# Sheet1.net
KiCad netlist of a schematic drawn in Altium Designer
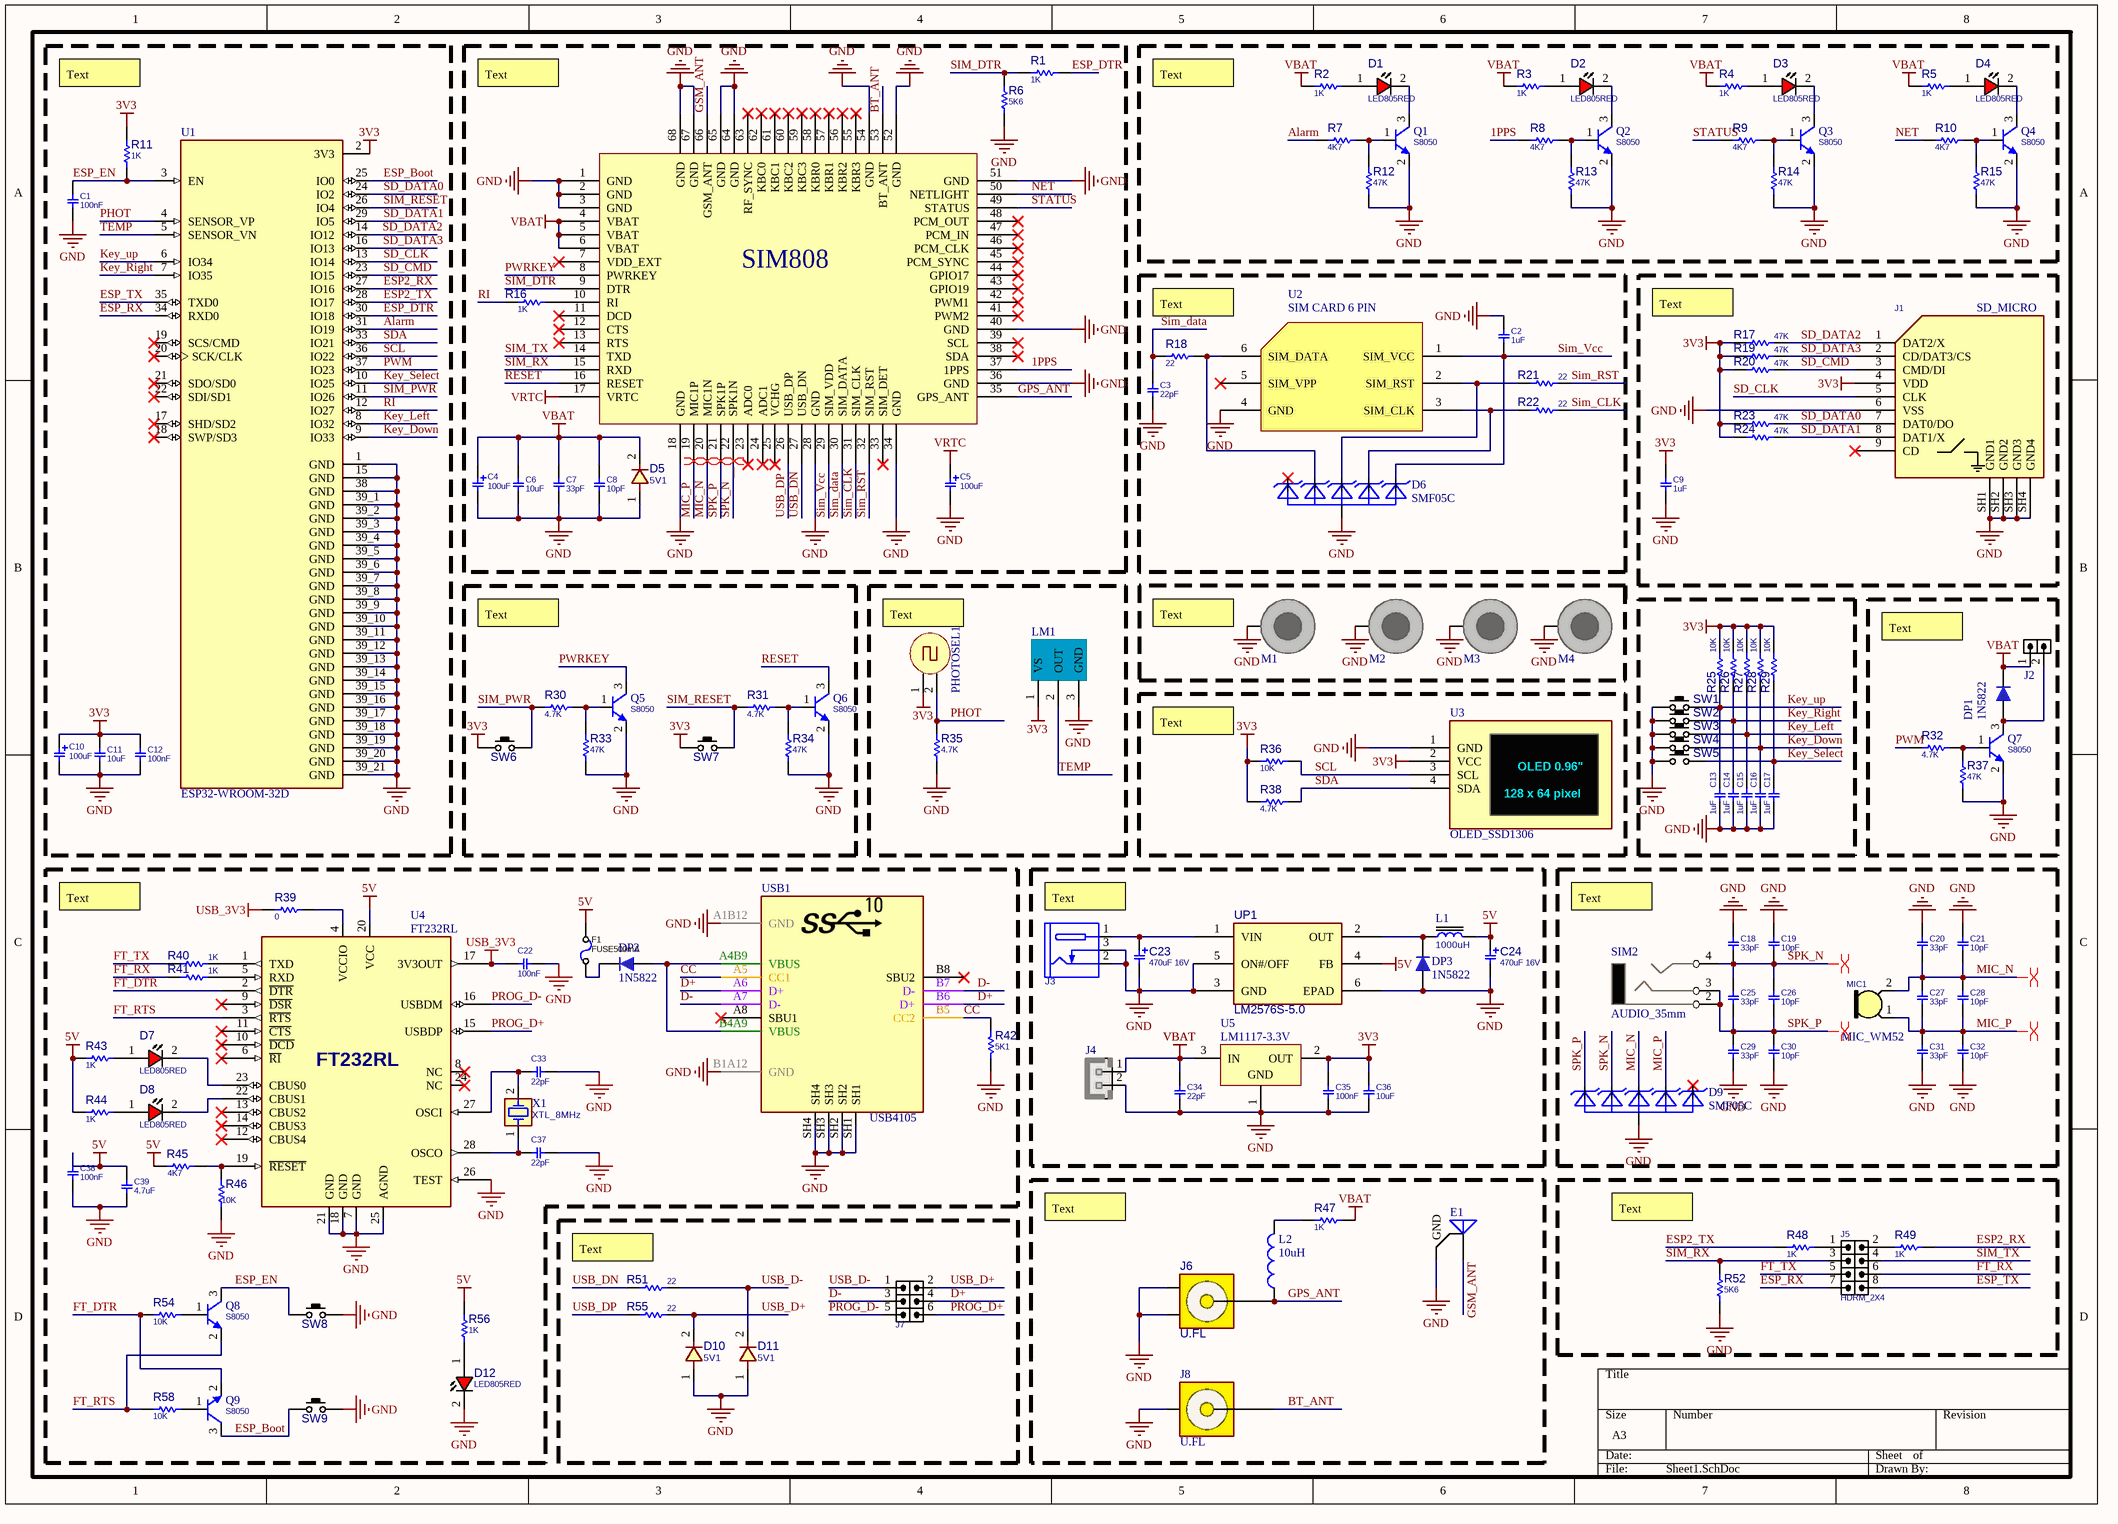
[diagram p0: Sheet1.SchDoc]

(export (version "E")
  (design (tool "Eeschema 10.0.6"))
  (components
    (comp (ref "C1")
      (value "100nF")
      (footprint "C0805")
      (description "CAP, MLCC, -F, -V, MATERIAL, -%, 0201")
      (fields (field (name "MANF_P#") "MANF_PART#"))
      (libsource (lib "Roller shutter") (part "CAP_SMD_MLCC_0805"))
    )
    (comp (ref "C2")
      (value "1uF")
      (footprint "C0805")
      (description "CAP, MLCC, -F, -V, MATERIAL, -%, 0201")
      (fields (field (name "MANF_P#") "MANF_PART#"))
      (libsource (lib "Roller shutter") (part "CAP_SMD_MLCC_0805"))
    )
    (comp (ref "C3")
      (value "22pF")
      (footprint "C0805")
      (description "CAP, MLCC, -F, -V, MATERIAL, -%, 0201")
      (fields (field (name "MANF_P#") "MANF_PART#"))
      (libsource (lib "Roller shutter") (part "CAP_SMD_MLCC_0805"))
    )
    (comp (ref "C4")
      (value "100uF")
      (footprint "C_TN_3528")
      (description "CAP, SMD, TAN")
      (fields (field (name "MANF") "AVX") (field (name "MANF_P#") "TCJT106M016R0200"))
      (libsource (lib "Call_GSM_SIM800L") (part "CAP_SMD_TAN_10uF_16V"))
    )
    (comp (ref "C5")
      (value "100uF")
      (footprint "C_TN_3528")
      (description "CAP, SMD, TAN")
      (fields (field (name "MANF") "AVX") (field (name "MANF_P#") "TCJT106M016R0200"))
      (libsource (lib "Call_GSM_SIM800L") (part "CAP_SMD_TAN_10uF_16V"))
    )
    (comp (ref "C6")
      (value "10uF")
      (footprint "C0805")
      (description "CAP, MLCC, -F, -V, MATERIAL, -%, 0201")
      (fields (field (name "MANF_P#") "MANF_PART#"))
      (libsource (lib "Roller shutter") (part "CAP_SMD_MLCC_0805"))
    )
    (comp (ref "C7")
      (value "33pF")
      (footprint "C0805")
      (description "CAP, MLCC, -F, -V, MATERIAL, -%, 0201")
      (fields (field (name "MANF_P#") "MANF_PART#"))
      (libsource (lib "Roller shutter") (part "CAP_SMD_MLCC_0805"))
    )
    (comp (ref "C8")
      (value "10pF")
      (footprint "C0805")
      (description "CAP, MLCC, -F, -V, MATERIAL, -%, 0201")
      (fields (field (name "MANF_P#") "MANF_PART#"))
      (libsource (lib "Roller shutter") (part "CAP_SMD_MLCC_0805"))
    )
    (comp (ref "C9")
      (value "1uF")
      (footprint "C0805")
      (description "CAP, MLCC, -F, -V, MATERIAL, -%, 0201")
      (fields (field (name "MANF_P#") "MANF_PART#"))
      (libsource (lib "Roller shutter") (part "CAP_SMD_MLCC_0805"))
    )
    (comp (ref "C10")
      (value "100uF")
      (footprint "C_TN_3528")
      (description "CAP, SMD, TAN")
      (fields (field (name "MANF") "AVX") (field (name "MANF_P#") "TCJT106M016R0200"))
      (libsource (lib "Call_GSM_SIM800L") (part "CAP_SMD_TAN_10uF_16V"))
    )
    (comp (ref "C11")
      (value "10uF")
      (footprint "C0805")
      (description "CAP, MLCC, -F, -V, MATERIAL, -%, 0201")
      (fields (field (name "MANF_P#") "MANF_PART#"))
      (libsource (lib "Roller shutter") (part "CAP_SMD_MLCC_0805"))
    )
    (comp (ref "C12")
      (value "100nF")
      (footprint "C0805")
      (description "CAP, MLCC, -F, -V, MATERIAL, -%, 0201")
      (fields (field (name "MANF_P#") "MANF_PART#"))
      (libsource (lib "Roller shutter") (part "CAP_SMD_MLCC_0805"))
    )
    (comp (ref "C13")
      (value "1uF")
      (footprint "C0805")
      (description "CAP, MLCC, -F, -V, MATERIAL, -%, 0201")
      (fields (field (name "MANF_P#") "MANF_PART#"))
      (libsource (lib "Roller shutter") (part "CAP_SMD_MLCC_0805"))
    )
    (comp (ref "C14")
      (value "1uF")
      (footprint "C0805")
      (description "CAP, MLCC, -F, -V, MATERIAL, -%, 0201")
      (fields (field (name "MANF_P#") "MANF_PART#"))
      (libsource (lib "Roller shutter") (part "CAP_SMD_MLCC_0805"))
    )
    (comp (ref "C15")
      (value "1uF")
      (footprint "C0805")
      (description "CAP, MLCC, -F, -V, MATERIAL, -%, 0201")
      (fields (field (name "MANF_P#") "MANF_PART#"))
      (libsource (lib "Roller shutter") (part "CAP_SMD_MLCC_0805"))
    )
    (comp (ref "C16")
      (value "1uF")
      (footprint "C0805")
      (description "CAP, MLCC, -F, -V, MATERIAL, -%, 0201")
      (fields (field (name "MANF_P#") "MANF_PART#"))
      (libsource (lib "Roller shutter") (part "CAP_SMD_MLCC_0805"))
    )
    (comp (ref "C17")
      (value "1uF")
      (footprint "C0805")
      (description "CAP, MLCC, -F, -V, MATERIAL, -%, 0201")
      (fields (field (name "MANF_P#") "MANF_PART#"))
      (libsource (lib "Roller shutter") (part "CAP_SMD_MLCC_0805"))
    )
    (comp (ref "C18")
      (value "33pF")
      (footprint "C0805")
      (description "CAP, MLCC, -F, -V, MATERIAL, -%, 0201")
      (fields (field (name "MANF_P#") "MANF_PART#"))
      (libsource (lib "Roller shutter") (part "CAP_SMD_MLCC_0805"))
    )
    (comp (ref "C19")
      (value "10pF")
      (footprint "C0805")
      (description "CAP, MLCC, -F, -V, MATERIAL, -%, 0201")
      (fields (field (name "MANF_P#") "MANF_PART#"))
      (libsource (lib "Roller shutter") (part "CAP_SMD_MLCC_0805"))
    )
    (comp (ref "C20")
      (value "33pF")
      (footprint "C0805")
      (description "CAP, MLCC, -F, -V, MATERIAL, -%, 0201")
      (fields (field (name "MANF_P#") "MANF_PART#"))
      (libsource (lib "Roller shutter") (part "CAP_SMD_MLCC_0805"))
    )
    (comp (ref "C21")
      (value "10pF")
      (footprint "C0805")
      (description "CAP, MLCC, -F, -V, MATERIAL, -%, 0201")
      (fields (field (name "MANF_P#") "MANF_PART#"))
      (libsource (lib "Roller shutter") (part "CAP_SMD_MLCC_0805"))
    )
    (comp (ref "C22")
      (value "100nF")
      (footprint "C0805")
      (description "CAP, MLCC, 1nF, 50V, C0G, 10%, 0402")
      (fields (field (name "MANF_P#") "MANF_PART#") (field (name "MANF") "Murata"))
      (libsource (lib "passive_smd") (part "CAP_SMD_MLCC"))
    )
    (comp (ref "C23")
      (value "470uF 16V")
      (footprint "C_EL_8")
      (description "CAP, SMDD, ELEC, 330uF, 25V")
      (fields (field (name "MANF_P#") "EEE-1EA331UP") (field (name "MANF") "PANASONIC"))
      (libsource (lib "QC_V2.0") (part "CAP_SMD_EL_330u25V"))
    )
    (comp (ref "C24")
      (value "470uF 16V")
      (footprint "C_EL_8")
      (description "CAP, SMDD, ELEC, 330uF, 25V")
      (fields (field (name "MANF_P#") "EEE-1EA331UP") (field (name "MANF") "PANASONIC"))
      (libsource (lib "QC_V2.0") (part "CAP_SMD_EL_330u25V"))
    )
    (comp (ref "C25")
      (value "33pF")
      (footprint "C0805")
      (description "CAP, MLCC, -F, -V, MATERIAL, -%, 0201")
      (fields (field (name "MANF_P#") "MANF_PART#"))
      (libsource (lib "Roller shutter") (part "CAP_SMD_MLCC_0805"))
    )
    (comp (ref "C26")
      (value "10pF")
      (footprint "C0805")
      (description "CAP, MLCC, -F, -V, MATERIAL, -%, 0201")
      (fields (field (name "MANF_P#") "MANF_PART#"))
      (libsource (lib "Roller shutter") (part "CAP_SMD_MLCC_0805"))
    )
    (comp (ref "C27")
      (value "33pF")
      (footprint "C0805")
      (description "CAP, MLCC, -F, -V, MATERIAL, -%, 0201")
      (fields (field (name "MANF_P#") "MANF_PART#"))
      (libsource (lib "Roller shutter") (part "CAP_SMD_MLCC_0805"))
    )
    (comp (ref "C28")
      (value "10pF")
      (footprint "C0805")
      (description "CAP, MLCC, -F, -V, MATERIAL, -%, 0201")
      (fields (field (name "MANF_P#") "MANF_PART#"))
      (libsource (lib "Roller shutter") (part "CAP_SMD_MLCC_0805"))
    )
    (comp (ref "C29")
      (value "33pF")
      (footprint "C0805")
      (description "CAP, MLCC, -F, -V, MATERIAL, -%, 0201")
      (fields (field (name "MANF_P#") "MANF_PART#"))
      (libsource (lib "Roller shutter") (part "CAP_SMD_MLCC_0805"))
    )
    (comp (ref "C30")
      (value "10pF")
      (footprint "C0805")
      (description "CAP, MLCC, -F, -V, MATERIAL, -%, 0201")
      (fields (field (name "MANF_P#") "MANF_PART#"))
      (libsource (lib "Roller shutter") (part "CAP_SMD_MLCC_0805"))
    )
    (comp (ref "C31")
      (value "33pF")
      (footprint "C0805")
      (description "CAP, MLCC, -F, -V, MATERIAL, -%, 0201")
      (fields (field (name "MANF_P#") "MANF_PART#"))
      (libsource (lib "Roller shutter") (part "CAP_SMD_MLCC_0805"))
    )
    (comp (ref "C32")
      (value "10pF")
      (footprint "C0805")
      (description "CAP, MLCC, -F, -V, MATERIAL, -%, 0201")
      (fields (field (name "MANF_P#") "MANF_PART#"))
      (libsource (lib "Roller shutter") (part "CAP_SMD_MLCC_0805"))
    )
    (comp (ref "C33")
      (value "22pF")
      (footprint "C0805")
      (description "CAP, MLCC, 1nF, 50V, C0G, 10%, 0402")
      (fields (field (name "MANF_P#") "MANF_PART#") (field (name "MANF") "Murata"))
      (libsource (lib "passive_smd") (part "CAP_SMD_MLCC"))
    )
    (comp (ref "C34")
      (value "22pF")
      (footprint "C0805")
      (description "CAP, MLCC, -F, -V, MATERIAL, -%, 0201")
      (fields (field (name "MANF_P#") "MANF_PART#"))
      (libsource (lib "Roller shutter") (part "CAP_SMD_MLCC_0805"))
    )
    (comp (ref "C35")
      (value "100nF")
      (footprint "C0805")
      (description "CAP, MLCC, -F, -V, MATERIAL, -%, 0201")
      (fields (field (name "MANF_P#") "MANF_PART#"))
      (libsource (lib "Roller shutter") (part "CAP_SMD_MLCC_0805"))
    )
    (comp (ref "C36")
      (value "10uF")
      (footprint "C0805")
      (description "CAP, MLCC, -F, -V, MATERIAL, -%, 0201")
      (fields (field (name "MANF_P#") "MANF_PART#"))
      (libsource (lib "Roller shutter") (part "CAP_SMD_MLCC_0805"))
    )
    (comp (ref "C37")
      (value "22pF")
      (footprint "C0805")
      (description "CAP, MLCC, 1nF, 50V, C0G, 10%, 0402")
      (fields (field (name "MANF_P#") "MANF_PART#") (field (name "MANF") "Murata"))
      (libsource (lib "passive_smd") (part "CAP_SMD_MLCC"))
    )
    (comp (ref "C38")
      (value "100nF")
      (footprint "C0805")
      (description "CAP, MLCC, 1nF, 50V, C0G, 10%, 0402")
      (fields (field (name "MANF_P#") "MANF_PART#") (field (name "MANF") "Murata"))
      (libsource (lib "passive_smd") (part "CAP_SMD_MLCC"))
    )
    (comp (ref "C39")
      (value "4.7uF")
      (footprint "C0805")
      (description "CAP, MLCC, 1nF, 50V, C0G, 10%, 0402")
      (fields (field (name "MANF_P#") "MANF_PART#") (field (name "MANF") "Murata"))
      (libsource (lib "passive_smd") (part "CAP_SMD_MLCC"))
    )
    (comp (ref "D1")
      (value "LED805RED")
      (footprint "LED0805RED")
      (description "LED, SMD, 0805, RED")
      (fields (field (name "MANF") "MANF") (field (name "MANF_P#") "MANF_PART#"))
      (libsource (lib "QC_V2.0") (part "LED_SMD_0805_RED"))
    )
    (comp (ref "D2")
      (value "LED805RED")
      (footprint "LED0805RED")
      (description "LED, SMD, 0805, RED")
      (fields (field (name "MANF") "MANF") (field (name "MANF_P#") "MANF_PART#"))
      (libsource (lib "QC_V2.0") (part "LED_SMD_0805_RED"))
    )
    (comp (ref "D3")
      (value "LED805RED")
      (footprint "LED0805RED")
      (description "LED, SMD, 0805, RED")
      (fields (field (name "MANF") "MANF") (field (name "MANF_P#") "MANF_PART#"))
      (libsource (lib "QC_V2.0") (part "LED_SMD_0805_RED"))
    )
    (comp (ref "D4")
      (value "LED805RED")
      (footprint "LED0805RED")
      (description "LED, SMD, 0805, RED")
      (fields (field (name "MANF") "MANF") (field (name "MANF_P#") "MANF_PART#"))
      (libsource (lib "QC_V2.0") (part "LED_SMD_0805_RED"))
    )
    (comp (ref "D5")
      (value "5V1")
      (footprint "D_SOD80")
      (description "DIODE, FAST SWTICHING, 0.3A, 0.5W")
      (fields (field (name "MANF") "MANF") (field (name "MANF_P#") "1N4148"))
      (libsource (lib "QC_V2.0") (part "DIODE_SMD_1N4148_SOD80"))
    )
    (comp (ref "D6")
      (value "SMF05C")
      (footprint "SMF05C")
      (description "12.5V Clamp 8A _8/20Âµs_ Ipp Tvs Diode Surface Mount SC-88/SC70-6/SOT-363")
      (fields (field (name "MF") "ON Semiconductor"))
      (libsource (lib "Call_GSM_SIM800L") (part "SMF05C"))
    )
    (comp (ref "D7")
      (value "LED805RED")
      (footprint "LED0805RED")
      (description "LED, SMD, 0805, RED")
      (fields (field (name "MANF") "MANF") (field (name "MANF_P#") "MANF_PART#"))
      (libsource (lib "led(diode)") (part "LED_SMD_0805_RED"))
    )
    (comp (ref "D8")
      (value "LED805RED")
      (footprint "LED0805RED")
      (description "LED, SMD, 0805, RED")
      (fields (field (name "MANF") "MANF") (field (name "MANF_P#") "MANF_PART#"))
      (libsource (lib "led(diode)") (part "LED_SMD_0805_RED"))
    )
    (comp (ref "D9")
      (value "SMF05C")
      (footprint "SMF05C")
      (description "12.5V Clamp 8A _8/20Âµs_ Ipp Tvs Diode Surface Mount SC-88/SC70-6/SOT-363")
      (fields (field (name "MF") "ON Semiconductor"))
      (libsource (lib "Call_GSM_SIM800L") (part "SMF05C"))
    )
    (comp (ref "D10")
      (value "5V1")
      (footprint "D_SOD80")
      (description "DIODE, FAST SWTICHING, 0.3A, 0.5W")
      (fields (field (name "MANF") "MANF") (field (name "MANF_P#") "1N4148"))
      (libsource (lib "sim808") (part "DIODE_SMD_1N4148_SOD80"))
    )
    (comp (ref "D11")
      (value "5V1")
      (footprint "D_SOD80")
      (description "DIODE, FAST SWTICHING, 0.3A, 0.5W")
      (fields (field (name "MANF") "MANF") (field (name "MANF_P#") "1N4148"))
      (libsource (lib "sim808") (part "DIODE_SMD_1N4148_SOD80"))
    )
    (comp (ref "D12")
      (value "LED805RED")
      (footprint "LED0805RED")
      (description "LED, SMD, 0805, RED")
      (fields (field (name "MANF") "MANF") (field (name "MANF_P#") "MANF_PART#"))
      (libsource (lib "led(diode)") (part "LED_SMD_0805_RED"))
    )
    (comp (ref "DP1")
      (value "1N5822")
      (footprint "430X270D")
      (description "Schottkey Rectifiers")
      (fields (field (name "DESIGNER") "Abbas Basereh"))
      (libsource (lib "Roller shutter") (part "1N5819"))
    )
    (comp (ref "DP2")
      (value "1N5822")
      (footprint "430X270D")
      (description "Schottkey Rectifiers")
      (fields (field (name "DESIGNER") "Abbas Basereh"))
      (libsource (lib "Roller shutter") (part "1N5819"))
    )
    (comp (ref "DP3")
      (value "1N5822")
      (footprint "430X270D")
      (description "Schottkey Rectifiers")
      (fields (field (name "DESIGNER") "Abbas Basereh"))
      (libsource (lib "Roller shutter") (part "1N5819"))
    )
    (comp (ref "E1")
      (value "Antenna")
      (footprint "SMA_Right")
      (description "Generic Antenna")
      (fields (field (name "PUBLISHER") "Altium Limited"))
      (libsource (lib "My_LIB") (part "Antenna"))
    )
    (comp (ref "F1")
      (value "FUSE500mA")
      (footprint "F0805")
      (description "Fuse, 500mA, 32VDC, 0805, SMD, Fast Acting")
      (fields (field (name "MANF") "MANF") (field (name "MANF_P#") "MANF_PART#"))
      (libsource (lib "protect_tvs_esd_fuse") (part "FUSE_500mA_0805_FAST"))
    )
    (comp (ref "J1")
      (value "SD_MICRO")
      (footprint "SDMICRO_AT")
      (description "SD MICRO exist in Iran, Attend 112J-TDAR-R01")
      (fields (field (name "MANF") "Attend") (field (name "MANF_P#") "112J-TDAR-R01"))
      (libsource (lib "socket_card") (part "SOCKET_SDMICRO_AT"))
    )
    (comp (ref "J2")
      (value "HDRM2")
      (footprint "HDR_M_1X2")
      (description "CONN, HEADER, Male, pitch: 2.54mm, 2POS")
      (libsource (lib "conn_header_2.54_st") (part "HDR_M_1X2"))
    )
    (comp (ref "J3")
      (value "DC_POWER_JACK")
      (footprint "JAC_PWR2")
      (description "CONN, PWR JACK DC, PLUG DIAM 2.0MM RA THD")
      (fields
        (field (name "MANF") "CUI STACK")
        (field (name "MANF_P#") "PJ-202A, PJ-002AH, PJ-102AH, KLDX-0202")
      )
      (libsource (lib "QC_V2.0") (part "CONN_PWR_JACKR2"))
    )
    (comp (ref "J4")
      (value "HHDR_2")
      (footprint "XH_2")
      (description "JST-XH pitch: 2.5mm")
      (libsource (lib "conn_wire2board") (part "XH_2"))
    )
    (comp (ref "J5")
      (value "HDRM_2X4")
      (footprint "HDR_M_2X4")
      (description "CONN, HEADER, Male, pitch: 2.54mm, 8POS")
      (fields (field (name "MANF_P#") "MANF_PART#") (field (name "MANF") "MANF"))
      (libsource (lib "conn_header_2.54_st") (part "HDR_M_2X4"))
    )
    (comp (ref "J6")
      (value "U.FL")
      (footprint "UFL")
      (description "CONN, RF, U.FL, STRAIGHT, Ultra Miniature Coaxial")
      (fields
        (field (name "MANF_P#") "CONUFL001-SMD, U.FL-R-SMT-1(10), 128-0711-201")
        (field (name "MANF") "Linx, Hirose, Cinch")
      )
      (libsource (lib "Call_GSM_SIM800L") (part "CONN_RF_UFL"))
    )
    (comp (ref "J7")
      (value "HDRM_2X3")
      (footprint "HDR_M_2X3")
      (description "CONN, HEADER, Male, pitch: 2.54mm, 6POS")
      (fields (field (name "MANF_P#") "MANF_PART#") (field (name "MANF") "MANF"))
      (libsource (lib "conn_header_2.54_st") (part "HDR_M_2X3"))
    )
    (comp (ref "J8")
      (value "U.FL")
      (footprint "2.4Ghz")
      (libsource (lib "Schlib") (part "BT & Wifi Anntena"))
    )
    (comp (ref "L1")
      (value "1000uH")
      (footprint "L_12")
      (description "INDUCTOR, POWER, SMD")
      (libsource (lib "QC_V2.0") (part "INDPWR_SMD"))
    )
    (comp (ref "L2")
      (value "10uH")
      (footprint "IND1206")
      (description "TOTAL INDUCTOR SMD PACK")
      (fields (field (name "DESIGNER") "Abbas Basereh"))
      (libsource (lib "Roller shutter") (part "INDUCTOR SMD PACKAGE"))
    )
    (comp (ref "LM1") (value "LM35") (footprint "TO-92B") (libsource (lib "SIM808") (part "LM35")))
    (comp (ref "M1")
      (value "DNP/MH")
      (footprint "SCMH_M3")
      (description "SCREW mouting, M3, 3.0mm diameter and 6.0mm PanHead")
      (libsource (lib "mech_mountingHole") (part "SCMH_M3"))
    )
    (comp (ref "M2")
      (value "DNP/MH")
      (footprint "SCMH_M3")
      (description "SCREW mouting, M3, 3.0mm diameter and 6.0mm PanHead")
      (libsource (lib "mech_mountingHole") (part "SCMH_M3"))
    )
    (comp (ref "M3")
      (value "DNP/MH")
      (footprint "SCMH_M3")
      (description "SCREW mouting, M3, 3.0mm diameter and 6.0mm PanHead")
      (libsource (lib "mech_mountingHole") (part "SCMH_M3"))
    )
    (comp (ref "M4")
      (value "DNP/MH")
      (footprint "SCMH_M3")
      (description "SCREW mouting, M3, 3.0mm diameter and 6.0mm PanHead")
      (libsource (lib "mech_mountingHole") (part "SCMH_M3"))
    )
    (comp (ref "MIC1")
      (value "MIC_WM52")
      (footprint "MIC_C9")
      (description "MICROPHONE OMNI")
      (fields (field (name "MANF_P#") "WM52BM"))
      (libsource (lib "audio_mic_spk") (part "MIC_WM-52"))
    )
    (comp (ref "PHOTOSEL1")
      (value "PHOTOSEL")
      (footprint "PHOTOSEL_3mm")
      (libsource (lib "SIM808") (part "PHOTOSEL"))
    )
    (comp (ref "Q1")
      (value "S8050")
      (footprint "SOT23_3")
      (description "BJT, NPN, 25v, 0.5A, SMD, SOT23")
      (libsource (lib "QC_V2.0") (part "NPN_S8050_SOT23"))
    )
    (comp (ref "Q2")
      (value "S8050")
      (footprint "SOT23_3")
      (description "BJT, NPN, 25v, 0.5A, SMD, SOT23")
      (libsource (lib "QC_V2.0") (part "NPN_S8050_SOT23"))
    )
    (comp (ref "Q3")
      (value "S8050")
      (footprint "SOT23_3")
      (description "BJT, NPN, 25v, 0.5A, SMD, SOT23")
      (libsource (lib "QC_V2.0") (part "NPN_S8050_SOT23"))
    )
    (comp (ref "Q4")
      (value "S8050")
      (footprint "SOT23_3")
      (description "BJT, NPN, 25v, 0.5A, SMD, SOT23")
      (libsource (lib "QC_V2.0") (part "NPN_S8050_SOT23"))
    )
    (comp (ref "Q5")
      (value "S8050")
      (footprint "SOT23_3")
      (description "BJT, NPN, 25v, 0.5A, SMD, SOT23")
      (libsource (lib "QC_V2.0") (part "NPN_S8050_SOT23"))
    )
    (comp (ref "Q6")
      (value "S8050")
      (footprint "SOT23_3")
      (description "BJT, NPN, 25v, 0.5A, SMD, SOT23")
      (libsource (lib "QC_V2.0") (part "NPN_S8050_SOT23"))
    )
    (comp (ref "Q7")
      (value "S8050")
      (footprint "SOT23_3")
      (description "BJT, NPN, 25v, 0.5A, SMD, SOT23")
      (libsource (lib "QC_V2.0") (part "NPN_S8050_SOT23"))
    )
    (comp (ref "Q8")
      (value "S8050")
      (footprint "SOT23_3")
      (description "BJT, NPN, 25v, 0.5A, SMD, SOT23")
      (libsource (lib "transistor_bjt") (part "NPN_S8050_SOT23"))
    )
    (comp (ref "Q9")
      (value "S8050")
      (footprint "SOT23_3")
      (description "BJT, NPN, 25v, 0.5A, SMD, SOT23")
      (libsource (lib "transistor_bjt") (part "NPN_S8050_SOT23"))
    )
    (comp (ref "R1")
      (value "1K")
      (footprint "R0805")
      (description "RESISTOR, SMD")
      (libsource (lib "QC_V2.0") (part "RES_SMD_0805"))
    )
    (comp (ref "R2")
      (value "1K")
      (footprint "R0805")
      (description "RESISTOR, SMD")
      (libsource (lib "QC_V2.0") (part "RES_SMD_0805"))
    )
    (comp (ref "R3")
      (value "1K")
      (footprint "R0805")
      (description "RESISTOR, SMD")
      (libsource (lib "QC_V2.0") (part "RES_SMD_0805"))
    )
    (comp (ref "R4")
      (value "1K")
      (footprint "R0805")
      (description "RESISTOR, SMD")
      (libsource (lib "QC_V2.0") (part "RES_SMD_0805"))
    )
    (comp (ref "R5")
      (value "1K")
      (footprint "R0805")
      (description "RESISTOR, SMD")
      (libsource (lib "QC_V2.0") (part "RES_SMD_0805"))
    )
    (comp (ref "R6")
      (value "5K6")
      (footprint "R0805")
      (description "RESISTOR, SMD")
      (libsource (lib "QC_V2.0") (part "RES_SMD_0805"))
    )
    (comp (ref "R7")
      (value "4K7")
      (footprint "R0805")
      (description "RESISTOR, SMD")
      (libsource (lib "QC_V2.0") (part "RES_SMD_0805"))
    )
    (comp (ref "R8")
      (value "4K7")
      (footprint "R0805")
      (description "RESISTOR, SMD")
      (libsource (lib "QC_V2.0") (part "RES_SMD_0805"))
    )
    (comp (ref "R9")
      (value "4K7")
      (footprint "R0805")
      (description "RESISTOR, SMD")
      (libsource (lib "QC_V2.0") (part "RES_SMD_0805"))
    )
    (comp (ref "R10")
      (value "4K7")
      (footprint "R0805")
      (description "RESISTOR, SMD")
      (libsource (lib "QC_V2.0") (part "RES_SMD_0805"))
    )
    (comp (ref "R11")
      (value "1K")
      (footprint "R0805")
      (description "RESISTOR, SMD")
      (libsource (lib "QC_V2.0") (part "RES_SMD_0805"))
    )
    (comp (ref "R12")
      (value "47K")
      (footprint "R0805")
      (description "RESISTOR, SMD")
      (libsource (lib "QC_V2.0") (part "RES_SMD_0805"))
    )
    (comp (ref "R13")
      (value "47K")
      (footprint "R0805")
      (description "RESISTOR, SMD")
      (libsource (lib "QC_V2.0") (part "RES_SMD_0805"))
    )
    (comp (ref "R14")
      (value "47K")
      (footprint "R0805")
      (description "RESISTOR, SMD")
      (libsource (lib "QC_V2.0") (part "RES_SMD_0805"))
    )
    (comp (ref "R15")
      (value "47K")
      (footprint "R0805")
      (description "RESISTOR, SMD")
      (libsource (lib "QC_V2.0") (part "RES_SMD_0805"))
    )
    (comp (ref "R16")
      (value "1K")
      (footprint "R0805")
      (description "RESISTOR, SMD")
      (libsource (lib "QC_V2.0") (part "RES_SMD_0805"))
    )
    (comp (ref "R17")
      (value "47K")
      (footprint "R0805")
      (description "RESISTOR, SMD")
      (libsource (lib "QC_V2.0") (part "RES_SMD_0805"))
    )
    (comp (ref "R18")
      (value "22")
      (footprint "R0805")
      (description "RESISTOR, SMD")
      (libsource (lib "QC_V2.0") (part "RES_SMD_0805"))
    )
    (comp (ref "R19")
      (value "47K")
      (footprint "R0805")
      (description "RESISTOR, SMD")
      (libsource (lib "QC_V2.0") (part "RES_SMD_0805"))
    )
    (comp (ref "R20")
      (value "47K")
      (footprint "R0805")
      (description "RESISTOR, SMD")
      (libsource (lib "QC_V2.0") (part "RES_SMD_0805"))
    )
    (comp (ref "R21")
      (value "22")
      (footprint "R0805")
      (description "RESISTOR, SMD")
      (libsource (lib "QC_V2.0") (part "RES_SMD_0805"))
    )
    (comp (ref "R22")
      (value "22")
      (footprint "R0805")
      (description "RESISTOR, SMD")
      (libsource (lib "QC_V2.0") (part "RES_SMD_0805"))
    )
    (comp (ref "R23")
      (value "47K")
      (footprint "R0805")
      (description "RESISTOR, SMD")
      (libsource (lib "QC_V2.0") (part "RES_SMD_0805"))
    )
    (comp (ref "R24")
      (value "47K")
      (footprint "R0805")
      (description "RESISTOR, SMD")
      (libsource (lib "QC_V2.0") (part "RES_SMD_0805"))
    )
    (comp (ref "R25")
      (value "10K")
      (footprint "R0805")
      (description "RESISTOR, SMD")
      (libsource (lib "QC_V2.0") (part "RES_SMD_0805"))
    )
    (comp (ref "R26")
      (value "10K")
      (footprint "R0805")
      (description "RESISTOR, SMD")
      (libsource (lib "QC_V2.0") (part "RES_SMD_0805"))
    )
    (comp (ref "R27")
      (value "10K")
      (footprint "R0805")
      (description "RESISTOR, SMD")
      (libsource (lib "QC_V2.0") (part "RES_SMD_0805"))
    )
    (comp (ref "R28")
      (value "10K")
      (footprint "R0805")
      (description "RESISTOR, SMD")
      (libsource (lib "QC_V2.0") (part "RES_SMD_0805"))
    )
    (comp (ref "R29")
      (value "10K")
      (footprint "R0805")
      (description "RESISTOR, SMD")
      (libsource (lib "QC_V2.0") (part "RES_SMD_0805"))
    )
    (comp (ref "R30")
      (value "4.7K")
      (footprint "R0805")
      (description "RESISTOR, SMD")
      (libsource (lib "QC_V2.0") (part "RES_SMD_0805"))
    )
    (comp (ref "R31")
      (value "4.7K")
      (footprint "R0805")
      (description "RESISTOR, SMD")
      (libsource (lib "QC_V2.0") (part "RES_SMD_0805"))
    )
    (comp (ref "R32")
      (value "4.7K")
      (footprint "R0805")
      (description "RESISTOR, SMD")
      (libsource (lib "QC_V2.0") (part "RES_SMD_0805"))
    )
    (comp (ref "R33")
      (value "47K")
      (footprint "R0805")
      (description "RESISTOR, SMD")
      (libsource (lib "QC_V2.0") (part "RES_SMD_0805"))
    )
    (comp (ref "R34")
      (value "47K")
      (footprint "R0805")
      (description "RESISTOR, SMD")
      (libsource (lib "QC_V2.0") (part "RES_SMD_0805"))
    )
    (comp (ref "R35")
      (value "4.7K")
      (footprint "R0805")
      (description "RESISTOR, SMD")
      (libsource (lib "QC_V2.0") (part "RES_SMD_0805"))
    )
    (comp (ref "R36")
      (value "10K")
      (footprint "R0805")
      (description "RESISTOR, SMD")
      (libsource (lib "QC_V2.0") (part "RES_SMD_0805"))
    )
    (comp (ref "R37")
      (value "47K")
      (footprint "R0805")
      (description "RESISTOR, SMD")
      (libsource (lib "QC_V2.0") (part "RES_SMD_0805"))
    )
    (comp (ref "R38")
      (value "4.7K")
      (footprint "R0805")
      (description "RESISTOR, SMD")
      (libsource (lib "QC_V2.0") (part "RES_SMD_0805"))
    )
    (comp (ref "R39")
      (value "0")
      (footprint "R0805")
      (description "RESISTOR, SMD")
      (libsource (lib "passive_smd") (part "RES_SMD_0805"))
    )
    (comp (ref "R40")
      (value "1K")
      (footprint "R0805")
      (description "RESISTOR, SMD")
      (libsource (lib "passive_smd") (part "RES_SMD_0805"))
    )
    (comp (ref "R41")
      (value "1K")
      (footprint "R0805")
      (description "RESISTOR, SMD")
      (libsource (lib "passive_smd") (part "RES_SMD_0805"))
    )
    (comp (ref "R42")
      (value "5K1")
      (footprint "R0805")
      (description "RESISTOR, SMD")
      (libsource (lib "QC_V2.0") (part "RES_SMD_0805"))
    )
    (comp (ref "R43")
      (value "1K")
      (footprint "R0805")
      (description "RESISTOR, SMD")
      (libsource (lib "passive_smd") (part "RES_SMD_0805"))
    )
    (comp (ref "R44")
      (value "1K")
      (footprint "R0805")
      (description "RESISTOR, SMD")
      (libsource (lib "passive_smd") (part "RES_SMD_0805"))
    )
    (comp (ref "R45")
      (value "4K7")
      (footprint "R0805")
      (description "RESISTOR, SMD")
      (libsource (lib "passive_smd") (part "RES_SMD_0805"))
    )
    (comp (ref "R46")
      (value "10K")
      (footprint "R0805")
      (description "RESISTOR, SMD")
      (libsource (lib "passive_smd") (part "RES_SMD_0805"))
    )
    (comp (ref "R47")
      (value "1K")
      (footprint "R0805")
      (description "RESISTOR, SMD")
      (libsource (lib "QC_V2.0") (part "RES_SMD_0805"))
    )
    (comp (ref "R48")
      (value "1K")
      (footprint "R0805")
      (description "RESISTOR, SMD")
      (libsource (lib "QC_V2.0") (part "RES_SMD_0805"))
    )
    (comp (ref "R49")
      (value "1K")
      (footprint "R0805")
      (description "RESISTOR, SMD")
      (libsource (lib "QC_V2.0") (part "RES_SMD_0805"))
    )
    (comp (ref "R51")
      (value "22")
      (footprint "R0805")
      (description "RESISTOR, SMD")
      (libsource (lib "QC_V2.0") (part "RES_SMD_0805"))
    )
    (comp (ref "R52")
      (value "5K6")
      (footprint "R0805")
      (description "RESISTOR, SMD")
      (libsource (lib "QC_V2.0") (part "RES_SMD_0805"))
    )
    (comp (ref "R54")
      (value "10K")
      (footprint "R0805")
      (description "RESISTOR, SMD")
      (libsource (lib "passive_smd") (part "RES_SMD_0805"))
    )
    (comp (ref "R55")
      (value "22")
      (footprint "R0805")
      (description "RESISTOR, SMD")
      (libsource (lib "QC_V2.0") (part "RES_SMD_0805"))
    )
    (comp (ref "R56")
      (value "1K")
      (footprint "R0805")
      (description "RESISTOR, SMD")
      (libsource (lib "passive_smd") (part "RES_SMD_0805"))
    )
    (comp (ref "R58")
      (value "10K")
      (footprint "R0805")
      (description "RESISTOR, SMD")
      (libsource (lib "passive_smd") (part "RES_SMD_0805"))
    )
    (comp (ref "SIM1") (value "sim808") (footprint "sim808_fp") (libsource (lib "SIM808") (part "sim808")))
    (comp (ref "SIM2")
      (value "AUDIO_35mm")
      (footprint "AUDIO_JACK2")
      (libsource (lib "SIM808") (part "AUDIO_NEW"))
    )
    (comp (ref "SW1")
      (value "PUSHBUTTON")
      (footprint "SWPBS_SPST_6X3X5")
      (description "SWITCH, PUSH BUTTON, TACTILE, SMD, SPST, 6X3.5X5mm")
      (fields (field (name "MANF") "ALPS") (field (name "MANF_P#") "SKQMBBE010"))
      (libsource (lib "QC_V2.0") (part "SWPBS_SPST_6X3X5"))
    )
    (comp (ref "SW2")
      (value "PUSHBUTTON")
      (footprint "SWPBS_SPST_6X3X5")
      (description "SWITCH, PUSH BUTTON, TACTILE, SMD, SPST, 6X3.5X5mm")
      (fields (field (name "MANF") "ALPS") (field (name "MANF_P#") "SKQMBBE010"))
      (libsource (lib "QC_V2.0") (part "SWPBS_SPST_6X3X5"))
    )
    (comp (ref "SW3")
      (value "PUSHBUTTON")
      (footprint "SWPBS_SPST_6X3X5")
      (description "SWITCH, PUSH BUTTON, TACTILE, SMD, SPST, 6X3.5X5mm")
      (fields (field (name "MANF") "ALPS") (field (name "MANF_P#") "SKQMBBE010"))
      (libsource (lib "QC_V2.0") (part "SWPBS_SPST_6X3X5"))
    )
    (comp (ref "SW4")
      (value "PUSHBUTTON")
      (footprint "SWPBS_SPST_6X3X5")
      (description "SWITCH, PUSH BUTTON, TACTILE, SMD, SPST, 6X3.5X5mm")
      (fields (field (name "MANF") "ALPS") (field (name "MANF_P#") "SKQMBBE010"))
      (libsource (lib "QC_V2.0") (part "SWPBS_SPST_6X3X5"))
    )
    (comp (ref "SW5")
      (value "PUSHBUTTON")
      (footprint "SWPBS_SPST_6X3X5")
      (description "SWITCH, PUSH BUTTON, TACTILE, SMD, SPST, 6X3.5X5mm")
      (fields (field (name "MANF") "ALPS") (field (name "MANF_P#") "SKQMBBE010"))
      (libsource (lib "QC_V2.0") (part "SWPBS_SPST_6X3X5"))
    )
    (comp (ref "SW6")
      (value "PUSHBUTTON")
      (footprint "SWPBS_SPST_6X3X5")
      (description "SWITCH, PUSH BUTTON, TACTILE, SMD, SPST, 6X3.5X5mm")
      (fields (field (name "MANF") "ALPS") (field (name "MANF_P#") "SKQMBBE010"))
      (libsource (lib "QC_V2.0") (part "SWPBS_SPST_6X3X5"))
    )
    (comp (ref "SW7")
      (value "PUSHBUTTON")
      (footprint "SWPBS_SPST_6X3X5")
      (description "SWITCH, PUSH BUTTON, TACTILE, SMD, SPST, 6X3.5X5mm")
      (fields (field (name "MANF") "ALPS") (field (name "MANF_P#") "SKQMBBE010"))
      (libsource (lib "QC_V2.0") (part "SWPBS_SPST_6X3X5"))
    )
    (comp (ref "SW8")
      (value "PUSHBUTTON")
      (footprint "SWPBS_SPST_6X3X5")
      (description "SWITCH, PUSH BUTTON, TACTILE, SMD, SPST, 6X3.5X5mm")
      (fields (field (name "MANF") "ALPS") (field (name "MANF_P#") "SKQMBBE010"))
      (libsource (lib "QC_V2.0") (part "SWPBS_SPST_6X3X5"))
    )
    (comp (ref "SW9")
      (value "PUSHBUTTON")
      (footprint "SWPBS_SPST_6X3X5")
      (description "SWITCH, PUSH BUTTON, TACTILE, SMD, SPST, 6X3.5X5mm")
      (fields (field (name "MANF") "ALPS") (field (name "MANF_P#") "SKQMBBE010"))
      (libsource (lib "QC_V2.0") (part "SWPBS_SPST_6X3X5"))
    )
    (comp (ref "U1")
      (value "ESP32-WROOM-32D")
      (footprint "MODULE_ESP32-WROOM-32D")
      (fields (field (name "MF") "Espressif Systems"))
      (libsource (lib "Roller shutter") (part "ESP32-WROOM-32D"))
    )
    (comp (ref "U2")
      (value "SIM CARD 6 PIN")
      (footprint "SIM CARD 6 PIN nano")
      (fields (field (name "PUBLISHER") "Bastam Beyrami"))
      (libsource (lib "SIM800C ARDUINO") (part "SIMCARD 6 PIN"))
    )
    (comp (ref "U3")
      (value "OLED_SSD1306")
      (footprint "OLED_SSD1306_64_I2C")
      (description "OLED, SSD1306, 0.96\", 128X64, BREAKOUT I2C")
      (fields (field (name "MANF_P#") "OLED_SSD1306_I2C"))
      (libsource (lib "lcd") (part "OLED_SSD1306_64_I2C"))
    )
    (comp (ref "U4")
      (value "FT232RL")
      (footprint "SOG65_28_W")
      (description "USB-UART, Asynchronous Serial Data Transfer Chip, SSOP-28")
      (fields (field (name "MANF") "FTDI"))
      (libsource (lib "usbic") (part "FT232RL_SSOP28"))
    )
    (comp (ref "U5")
      (value "LM1117-3.3V")
      (footprint "LM1117_SMD_SOT-223_3.3V")
      (libsource (lib "Roller shutter") (part "LM1117_SMD_SOT-223"))
    )
    (comp (ref "UP1")
      (value "LM2576S-5.0")
      (footprint "D2PAK_5")
      (description "REG, Switching, Buck, 3A, 5V, 50KHz, TO-220")
      (fields (field (name "MANF") "TI, ON, HTC, MICROCHIP"))
      (libsource (lib "pwr_switching_buck_hv") (part "VREG_LM2576S-5.0"))
    )
    (comp (ref "USB1")
      (value "USB4105")
      (footprint "USBC_SMD_16_USB4105")
      (description "CONN, USB, Type C, USB 2.0, Right-Angle, SMD")
      (fields (field (name "MANF") "GCT") (field (name "MANF_P#") "USB4105-GF-A"))
      (libsource (lib "CH340_TypeC_V2") (part "CONN_USBC_SMD_16_USB4105"))
    )
    (comp (ref "X1")
      (value "XTL_8MHz")
      (footprint "XTL_2_11X5")
      (description "Crystal MOST POPULAR ABL HC49 PACKAGE")
      (fields (field (name "MANF") "ABRACON") (field (name "MANF_P#") "ABLS-8.000MHZ-B4-T"))
      (libsource (lib "crystal") (part "XTL_2_HC49_8MHz_SMD"))
    )
  )
  (nets
    (net (code "1") (name "/1PPS") (class "Default")
      (node (ref "R8") (pin "1") (pinfunction "1_1") (pintype "passive"))
      (node (ref "SIM1") (pin "37") (pinfunction "1PPS_37") (pintype "passive"))
    )
    (net (code "2") (name "/Alarm") (class "Default")
      (node (ref "R7") (pin "1") (pinfunction "1_1") (pintype "passive"))
      (node (ref "U1") (pin "31") (pinfunction "IO19_31") (pintype "bidirectional"))
    )
    (net (code "3") (name "/BT_ANT") (class "Default")
      (node (ref "J8") (pin "1") (pinfunction "SIG_1") (pintype "passive"))
      (node (ref "SIM1") (pin "53") (pinfunction "BT_ANT_53") (pintype "passive"))
    )
    (net (code "4") (name "/CC") (class "Default")
      (node (ref "R42") (pin "2") (pinfunction "2_2") (pintype "passive"))
      (node (ref "USB1") (pin "A5") (pinfunction "CC1_A5") (pintype "passive"))
      (node (ref "USB1") (pin "B5") (pinfunction "CC2_B5") (pintype "passive"))
    )
    (net (code "5") (name "/D+") (class "Default")
      (node (ref "J7") (pin "4") (pinfunction "4_4") (pintype "passive"))
      (node (ref "USB1") (pin "A6") (pinfunction "D+_A6") (pintype "passive"))
      (node (ref "USB1") (pin "B6") (pinfunction "D+_B6") (pintype "passive"))
    )
    (net (code "6") (name "/D-") (class "Default")
      (node (ref "J7") (pin "3") (pinfunction "3_3") (pintype "passive"))
      (node (ref "USB1") (pin "A7") (pinfunction "D-_A7") (pintype "passive"))
      (node (ref "USB1") (pin "B7") (pinfunction "D-_B7") (pintype "passive"))
    )
    (net (code "7") (name "/ESP2_RX") (class "Default")
      (node (ref "R49") (pin "1") (pinfunction "1_1") (pintype "passive"))
      (node (ref "U1") (pin "27") (pinfunction "IO16_27") (pintype "bidirectional"))
    )
    (net (code "8") (name "/ESP2_TX") (class "Default")
      (node (ref "R48") (pin "2") (pinfunction "2_2") (pintype "passive"))
      (node (ref "U1") (pin "28") (pinfunction "IO17_28") (pintype "bidirectional"))
    )
    (net (code "9") (name "/ESP_Boot") (class "Default")
      (node (ref "Q9") (pin "3") (pinfunction "C_3") (pintype "passive"))
      (node (ref "SW9") (pin "1") (pinfunction "P1_1") (pintype "passive"))
      (node (ref "U1") (pin "25") (pinfunction "IO0_25") (pintype "bidirectional"))
    )
    (net (code "10") (name "/ESP_DTR") (class "Default")
      (node (ref "R1") (pin "1") (pinfunction "1_1") (pintype "passive"))
      (node (ref "U1") (pin "30") (pinfunction "IO18_30") (pintype "bidirectional"))
    )
    (net (code "11") (name "/ESP_EN") (class "Default")
      (node (ref "C1") (pin "1") (pinfunction "1_1") (pintype "passive"))
      (node (ref "Q8") (pin "3") (pinfunction "C_3") (pintype "passive"))
      (node (ref "R11") (pin "2") (pinfunction "2_2") (pintype "passive"))
      (node (ref "SW8") (pin "1") (pinfunction "P1_1") (pintype "passive"))
      (node (ref "U1") (pin "3") (pinfunction "EN_3") (pintype "input"))
    )
    (net (code "12") (name "/ESP_RX") (class "Default")
      (node (ref "J5") (pin "7") (pinfunction "7_7") (pintype "passive"))
      (node (ref "U1") (pin "34") (pinfunction "RXD0_34") (pintype "bidirectional"))
    )
    (net (code "13") (name "/ESP_TX") (class "Default")
      (node (ref "J5") (pin "8") (pinfunction "8_8") (pintype "passive"))
      (node (ref "U1") (pin "35") (pinfunction "TXD0_35") (pintype "bidirectional"))
    )
    (net (code "14") (name "/FT_DTR") (class "Default")
      (node (ref "Q9") (pin "2") (pinfunction "E_2") (pintype "passive"))
      (node (ref "R54") (pin "1") (pinfunction "1_1") (pintype "passive"))
      (node (ref "U4") (pin "2") (pinfunction "~{DTR}_2") (pintype "output"))
    )
    (net (code "15") (name "/FT_RTS") (class "Default")
      (node (ref "Q8") (pin "2") (pinfunction "E_2") (pintype "passive"))
      (node (ref "R58") (pin "1") (pinfunction "1_1") (pintype "passive"))
      (node (ref "U4") (pin "3") (pinfunction "~{RTS}_3") (pintype "output"))
    )
    (net (code "16") (name "/FT_RX") (class "Default")
      (node (ref "J5") (pin "6") (pinfunction "6_6") (pintype "passive"))
      (node (ref "R41") (pin "1") (pinfunction "1_1") (pintype "passive"))
    )
    (net (code "17") (name "/FT_TX") (class "Default")
      (node (ref "J5") (pin "5") (pinfunction "5_5") (pintype "passive"))
      (node (ref "R40") (pin "1") (pinfunction "1_1") (pintype "passive"))
    )
    (net (code "18") (name "/GPS_ANT") (class "Default")
      (node (ref "J6") (pin "1") (pinfunction "SIG_1") (pintype "passive"))
      (node (ref "L2") (pin "1") (pinfunction "1_1") (pintype "passive"))
      (node (ref "SIM1") (pin "35") (pinfunction "GPS_ANT_35") (pintype "passive"))
    )
    (net (code "19") (name "/GSM_ANT") (class "Default")
      (node (ref "E1") (pin "1") (pinfunction "A_1") (pintype "passive"))
      (node (ref "SIM1") (pin "66") (pinfunction "GSM_ANT_66") (pintype "passive"))
    )
    (net (code "20") (name "/Key_Down") (class "Default")
      (node (ref "C16") (pin "2") (pinfunction "2_2") (pintype "passive"))
      (node (ref "R28") (pin "1") (pinfunction "1_1") (pintype "passive"))
      (node (ref "SW4") (pin "2") (pinfunction "P3_2") (pintype "passive"))
      (node (ref "U1") (pin "9") (pinfunction "IO33_9") (pintype "bidirectional"))
    )
    (net (code "21") (name "/Key_Left") (class "Default")
      (node (ref "C15") (pin "2") (pinfunction "2_2") (pintype "passive"))
      (node (ref "R27") (pin "1") (pinfunction "1_1") (pintype "passive"))
      (node (ref "SW3") (pin "2") (pinfunction "P3_2") (pintype "passive"))
      (node (ref "U1") (pin "8") (pinfunction "IO32_8") (pintype "bidirectional"))
    )
    (net (code "22") (name "/Key_Right") (class "Default")
      (node (ref "C14") (pin "2") (pinfunction "2_2") (pintype "passive"))
      (node (ref "R26") (pin "1") (pinfunction "1_1") (pintype "passive"))
      (node (ref "SW2") (pin "2") (pinfunction "P3_2") (pintype "passive"))
      (node (ref "U1") (pin "7") (pinfunction "IO35_7") (pintype "input"))
    )
    (net (code "23") (name "/Key_Select") (class "Default")
      (node (ref "C17") (pin "2") (pinfunction "2_2") (pintype "passive"))
      (node (ref "R29") (pin "1") (pinfunction "1_1") (pintype "passive"))
      (node (ref "SW5") (pin "2") (pinfunction "P3_2") (pintype "passive"))
      (node (ref "U1") (pin "10") (pinfunction "IO25_10") (pintype "bidirectional"))
    )
    (net (code "24") (name "/Key_up") (class "Default")
      (node (ref "C13") (pin "2") (pinfunction "2_2") (pintype "passive"))
      (node (ref "R25") (pin "1") (pinfunction "1_1") (pintype "passive"))
      (node (ref "SW1") (pin "2") (pinfunction "P3_2") (pintype "passive"))
      (node (ref "U1") (pin "6") (pinfunction "IO34_6") (pintype "input"))
    )
    (net (code "25") (name "/MIC_N") (class "Default")
      (node (ref "C20") (pin "1") (pinfunction "1_1") (pintype "passive"))
      (node (ref "C21") (pin "1") (pinfunction "1_1") (pintype "passive"))
      (node (ref "C27") (pin "2") (pinfunction "2_2") (pintype "passive"))
      (node (ref "C28") (pin "2") (pinfunction "2_2") (pintype "passive"))
      (node (ref "D9") (pin "4") (pinfunction "C3_4") (pintype "passive"))
      (node (ref "MIC1") (pin "2") (pinfunction "GND_2") (pintype "passive"))
      (node (ref "SIM1") (pin "20") (pinfunction "MIC1N_20") (pintype "passive"))
    )
    (net (code "26") (name "/MIC_P") (class "Default")
      (node (ref "C27") (pin "1") (pinfunction "1_1") (pintype "passive"))
      (node (ref "C28") (pin "1") (pinfunction "1_1") (pintype "passive"))
      (node (ref "C31") (pin "2") (pinfunction "2_2") (pintype "passive"))
      (node (ref "C32") (pin "2") (pinfunction "2_2") (pintype "passive"))
      (node (ref "D9") (pin "5") (pinfunction "C4_5") (pintype "passive"))
      (node (ref "MIC1") (pin "1") (pinfunction "OUT_1") (pintype "passive"))
      (node (ref "SIM1") (pin "19") (pinfunction "MIC1P_19") (pintype "passive"))
    )
    (net (code "27") (name "/NET") (class "Default")
      (node (ref "R10") (pin "1") (pinfunction "1_1") (pintype "passive"))
      (node (ref "SIM1") (pin "50") (pinfunction "NETLIGHT_50") (pintype "passive"))
    )
    (net (code "28") (name "/PHOT") (class "Default")
      (node (ref "PHOTOSEL1") (pin "2") (pinfunction "2_2") (pintype "passive"))
      (node (ref "R35") (pin "2") (pinfunction "2_2") (pintype "passive"))
      (node (ref "U1") (pin "4") (pinfunction "SENSOR_VP_4") (pintype "input"))
    )
    (net (code "29") (name "/PROG_D+") (class "Default")
      (node (ref "J7") (pin "6") (pinfunction "6_6") (pintype "passive"))
      (node (ref "U4") (pin "15") (pinfunction "USBDP_15") (pintype "bidirectional"))
    )
    (net (code "30") (name "/PROG_D-") (class "Default")
      (node (ref "J7") (pin "5") (pinfunction "5_5") (pintype "passive"))
      (node (ref "U4") (pin "16") (pinfunction "USBDM_16") (pintype "bidirectional"))
    )
    (net (code "31") (name "/PWM") (class "Default")
      (node (ref "R32") (pin "1") (pinfunction "1_1") (pintype "passive"))
      (node (ref "U1") (pin "37") (pinfunction "IO23_37") (pintype "bidirectional"))
    )
    (net (code "32") (name "/PWRKEY") (class "Default")
      (node (ref "Q5") (pin "3") (pinfunction "C_3") (pintype "passive"))
      (node (ref "SIM1") (pin "8") (pinfunction "PWRKEY_8") (pintype "passive"))
    )
    (net (code "33") (name "/RESET") (class "Default")
      (node (ref "Q6") (pin "3") (pinfunction "C_3") (pintype "passive"))
      (node (ref "SIM1") (pin "16") (pinfunction "RESET_16") (pintype "passive"))
    )
    (net (code "34") (name "/RI") (class "Default")
      (node (ref "R16") (pin "2") (pinfunction "2_2") (pintype "passive"))
      (node (ref "U1") (pin "12") (pinfunction "IO27_12") (pintype "bidirectional"))
    )
    (net (code "35") (name "/SCL") (class "Default")
      (node (ref "R36") (pin "2") (pinfunction "2_2") (pintype "passive"))
      (node (ref "U1") (pin "36") (pinfunction "IO22_36") (pintype "bidirectional"))
      (node (ref "U3") (pin "3") (pinfunction "SCL_3") (pintype "passive"))
    )
    (net (code "36") (name "/SDA") (class "Default")
      (node (ref "R38") (pin "1") (pinfunction "1_1") (pintype "passive"))
      (node (ref "U1") (pin "33") (pinfunction "IO21_33") (pintype "bidirectional"))
      (node (ref "U3") (pin "4") (pinfunction "SDA_4") (pintype "passive"))
    )
    (net (code "37") (name "/SD_CLK") (class "Default")
      (node (ref "J1") (pin "5") (pinfunction "CLK_5") (pintype "passive"))
      (node (ref "U1") (pin "13") (pinfunction "IO14_13") (pintype "bidirectional"))
    )
    (net (code "38") (name "/SD_CMD") (class "Default")
      (node (ref "J1") (pin "3") (pinfunction "CMD/DI_3") (pintype "passive"))
      (node (ref "R20") (pin "1") (pinfunction "1_1") (pintype "passive"))
      (node (ref "U1") (pin "23") (pinfunction "IO15_23") (pintype "bidirectional"))
    )
    (net (code "39") (name "/SD_DATA0") (class "Default")
      (node (ref "J1") (pin "7") (pinfunction "DAT0/DO_7") (pintype "passive"))
      (node (ref "R23") (pin "1") (pinfunction "1_1") (pintype "passive"))
      (node (ref "U1") (pin "24") (pinfunction "IO2_24") (pintype "bidirectional"))
    )
    (net (code "40") (name "/SD_DATA1") (class "Default")
      (node (ref "J1") (pin "8") (pinfunction "DAT1/X_8") (pintype "passive"))
      (node (ref "R24") (pin "1") (pinfunction "1_1") (pintype "passive"))
      (node (ref "U1") (pin "29") (pinfunction "IO5_29") (pintype "bidirectional"))
    )
    (net (code "41") (name "/SD_DATA2") (class "Default")
      (node (ref "J1") (pin "1") (pinfunction "DAT2/X_1") (pintype "passive"))
      (node (ref "R17") (pin "1") (pinfunction "1_1") (pintype "passive"))
      (node (ref "U1") (pin "14") (pinfunction "IO12_14") (pintype "bidirectional"))
    )
    (net (code "42") (name "/SD_DATA3") (class "Default")
      (node (ref "J1") (pin "2") (pinfunction "CD/DAT3/CS_2") (pintype "passive"))
      (node (ref "R19") (pin "1") (pinfunction "1_1") (pintype "passive"))
      (node (ref "U1") (pin "16") (pinfunction "IO13_16") (pintype "bidirectional"))
    )
    (net (code "43") (name "/SIM_DTR") (class "Default")
      (node (ref "R1") (pin "2") (pinfunction "2_2") (pintype "passive"))
      (node (ref "R6") (pin "2") (pinfunction "2_2") (pintype "passive"))
      (node (ref "SIM1") (pin "9") (pinfunction "DTR_9") (pintype "passive"))
    )
    (net (code "44") (name "/SIM_PWR") (class "Default")
      (node (ref "R30") (pin "1") (pinfunction "1_1") (pintype "passive"))
      (node (ref "SW6") (pin "2") (pinfunction "P3_2") (pintype "passive"))
      (node (ref "U1") (pin "11") (pinfunction "IO26_11") (pintype "bidirectional"))
    )
    (net (code "45") (name "/SIM_RESET") (class "Default")
      (node (ref "R31") (pin "1") (pinfunction "1_1") (pintype "passive"))
      (node (ref "SW7") (pin "2") (pinfunction "P3_2") (pintype "passive"))
      (node (ref "U1") (pin "26") (pinfunction "IO4_26") (pintype "bidirectional"))
    )
    (net (code "46") (name "/SIM_RX") (class "Default")
      (node (ref "J5") (pin "3") (pinfunction "3_3") (pintype "passive"))
      (node (ref "R52") (pin "2") (pinfunction "2_2") (pintype "passive"))
      (node (ref "SIM1") (pin "15") (pinfunction "RXD_15") (pintype "passive"))
    )
    (net (code "47") (name "/SIM_TX") (class "Default")
      (node (ref "J5") (pin "4") (pinfunction "4_4") (pintype "passive"))
      (node (ref "SIM1") (pin "14") (pinfunction "TXD_14") (pintype "passive"))
    )
    (net (code "48") (name "/SPK_N") (class "Default")
      (node (ref "C18") (pin "1") (pinfunction "1_1") (pintype "passive"))
      (node (ref "C19") (pin "2") (pinfunction "2_2") (pintype "passive"))
      (node (ref "C25") (pin "2") (pinfunction "2_2") (pintype "passive"))
      (node (ref "C26") (pin "2") (pinfunction "2_2") (pintype "passive"))
      (node (ref "D9") (pin "3") (pinfunction "C2_3") (pintype "passive"))
      (node (ref "SIM1") (pin "22") (pinfunction "SPK1N_22") (pintype "passive"))
      (node (ref "SIM2") (pin "4") (pinfunction "2_4") (pintype "passive"))
    )
    (net (code "49") (name "/SPK_P") (class "Default")
      (node (ref "C25") (pin "1") (pinfunction "1_1") (pintype "passive"))
      (node (ref "C26") (pin "1") (pinfunction "1_1") (pintype "passive"))
      (node (ref "C29") (pin "2") (pinfunction "2_2") (pintype "passive"))
      (node (ref "C30") (pin "2") (pinfunction "2_2") (pintype "passive"))
      (node (ref "D9") (pin "1") (pinfunction "C1_1") (pintype "passive"))
      (node (ref "SIM1") (pin "21") (pinfunction "SPK1P_21") (pintype "passive"))
      (node (ref "SIM2") (pin "2") (pinfunction "2_2") (pintype "passive"))
      (node (ref "SIM2") (pin "3") (pinfunction "3_3") (pintype "passive"))
    )
    (net (code "50") (name "/STATUS") (class "Default")
      (node (ref "R9") (pin "1") (pinfunction "1_1") (pintype "passive"))
      (node (ref "SIM1") (pin "49") (pinfunction "STATUS_49") (pintype "passive"))
    )
    (net (code "51") (name "/Sim_CLK") (class "Default")
      (node (ref "R22") (pin "1") (pinfunction "1_1") (pintype "passive"))
      (node (ref "SIM1") (pin "31") (pinfunction "SIM_CLK_31") (pintype "passive"))
    )
    (net (code "52") (name "/Sim_RST") (class "Default")
      (node (ref "R21") (pin "1") (pinfunction "1_1") (pintype "passive"))
      (node (ref "SIM1") (pin "32") (pinfunction "SIM_RST_32") (pintype "passive"))
    )
    (net (code "53") (name "/Sim_Vcc") (class "Default")
      (node (ref "C2") (pin "2") (pinfunction "2_2") (pintype "passive"))
      (node (ref "D6") (pin "6") (pinfunction "C5_6") (pintype "passive"))
      (node (ref "SIM1") (pin "29") (pinfunction "SIM_VDD_29") (pintype "passive"))
      (node (ref "U2") (pin "1") (pinfunction "SIM_VCC_1") (pintype "passive"))
    )
    (net (code "54") (name "/Sim_data") (class "Default")
      (node (ref "C3") (pin "2") (pinfunction "2_2") (pintype "passive"))
      (node (ref "R18") (pin "2") (pinfunction "2_2") (pintype "passive"))
      (node (ref "SIM1") (pin "30") (pinfunction "SIM_DATA_30") (pintype "passive"))
    )
    (net (code "55") (name "/TEMP") (class "Default")
      (node (ref "LM1") (pin "2") (pinfunction "OUT_2") (pintype "passive"))
      (node (ref "U1") (pin "5") (pinfunction "SENSOR_VN_5") (pintype "input"))
    )
    (net (code "56") (name "/USB_D+") (class "Default")
      (node (ref "D10") (pin "2") (pinfunction "2_2") (pintype "passive"))
      (node (ref "J7") (pin "2") (pinfunction "2_2") (pintype "passive"))
      (node (ref "R55") (pin "1") (pinfunction "1_1") (pintype "passive"))
    )
    (net (code "57") (name "/USB_D-") (class "Default")
      (node (ref "D11") (pin "2") (pinfunction "2_2") (pintype "passive"))
      (node (ref "J7") (pin "1") (pinfunction "1_1") (pintype "passive"))
      (node (ref "R51") (pin "1") (pinfunction "1_1") (pintype "passive"))
    )
    (net (code "58") (name "/USB_DN") (class "Default")
      (node (ref "R51") (pin "2") (pinfunction "2_2") (pintype "passive"))
      (node (ref "SIM1") (pin "27") (pinfunction "USB_DN_27") (pintype "passive"))
    )
    (net (code "59") (name "/USB_DP") (class "Default")
      (node (ref "R55") (pin "2") (pinfunction "2_2") (pintype "passive"))
      (node (ref "SIM1") (pin "26") (pinfunction "USB_DP_26") (pintype "passive"))
    )
    (net (code "60") (name "3V3") (class "Default")
      (node (ref "C10") (pin "1") (pinfunction "1_1") (pintype "passive"))
      (node (ref "C11") (pin "1") (pinfunction "1_1") (pintype "passive"))
      (node (ref "C12") (pin "1") (pinfunction "1_1") (pintype "passive"))
      (node (ref "C35") (pin "2") (pinfunction "2_2") (pintype "passive"))
      (node (ref "C36") (pin "2") (pinfunction "2_2") (pintype "passive"))
      (node (ref "C9") (pin "1") (pinfunction "1_1") (pintype "passive"))
      (node (ref "J1") (pin "4") (pinfunction "VDD_4") (pintype "passive"))
      (node (ref "LM1") (pin "1") (pinfunction "VS_1") (pintype "passive"))
      (node (ref "PHOTOSEL1") (pin "1") (pinfunction "1_1") (pintype "passive"))
      (node (ref "R11") (pin "1") (pinfunction "1_1") (pintype "passive"))
      (node (ref "R17") (pin "2") (pinfunction "2_2") (pintype "passive"))
      (node (ref "R19") (pin "2") (pinfunction "2_2") (pintype "passive"))
      (node (ref "R20") (pin "2") (pinfunction "2_2") (pintype "passive"))
      (node (ref "R23") (pin "2") (pinfunction "2_2") (pintype "passive"))
      (node (ref "R24") (pin "2") (pinfunction "2_2") (pintype "passive"))
      (node (ref "R25") (pin "2") (pinfunction "2_2") (pintype "passive"))
      (node (ref "R26") (pin "2") (pinfunction "2_2") (pintype "passive"))
      (node (ref "R27") (pin "2") (pinfunction "2_2") (pintype "passive"))
      (node (ref "R28") (pin "2") (pinfunction "2_2") (pintype "passive"))
      (node (ref "R29") (pin "2") (pinfunction "2_2") (pintype "passive"))
      (node (ref "R36") (pin "1") (pinfunction "1_1") (pintype "passive"))
      (node (ref "R38") (pin "2") (pinfunction "2_2") (pintype "passive"))
      (node (ref "SW6") (pin "1") (pinfunction "P1_1") (pintype "passive"))
      (node (ref "SW7") (pin "1") (pinfunction "P1_1") (pintype "passive"))
      (node (ref "U1") (pin "2") (pinfunction "3V3_2") (pintype "power_in"))
      (node (ref "U3") (pin "2") (pinfunction "VCC_2") (pintype "passive"))
      (node (ref "U5") (pin "2") (pinfunction "OUT_2") (pintype "power_in"))
    )
    (net (code "61") (name "5V") (class "Default")
      (node (ref "C24") (pin "1") (pinfunction "1_1") (pintype "passive"))
      (node (ref "C38") (pin "2") (pinfunction "2_2") (pintype "passive"))
      (node (ref "C39") (pin "2") (pinfunction "2_2") (pintype "passive"))
      (node (ref "F1") (pin "1") (pinfunction "1_1") (pintype "passive"))
      (node (ref "L1") (pin "2") (pinfunction "2_2") (pintype "passive"))
      (node (ref "R43") (pin "1") (pinfunction "1_1") (pintype "passive"))
      (node (ref "R44") (pin "1") (pinfunction "1_1") (pintype "passive"))
      (node (ref "R45") (pin "2") (pinfunction "2_2") (pintype "passive"))
      (node (ref "R56") (pin "1") (pinfunction "1_1") (pintype "passive"))
      (node (ref "U4") (pin "20") (pinfunction "VCC_20") (pintype "power_in"))
      (node (ref "UP1") (pin "4") (pinfunction "FB_4") (pintype "passive"))
    )
    (net (code "62") (name "GND") (class "Default")
      (node (ref "C1") (pin "2") (pinfunction "2_2") (pintype "passive"))
      (node (ref "C10") (pin "2") (pinfunction "2_2") (pintype "passive"))
      (node (ref "C11") (pin "2") (pinfunction "2_2") (pintype "passive"))
      (node (ref "C12") (pin "2") (pinfunction "2_2") (pintype "passive"))
      (node (ref "C13") (pin "1") (pinfunction "1_1") (pintype "passive"))
      (node (ref "C14") (pin "1") (pinfunction "1_1") (pintype "passive"))
      (node (ref "C15") (pin "1") (pinfunction "1_1") (pintype "passive"))
      (node (ref "C16") (pin "1") (pinfunction "1_1") (pintype "passive"))
      (node (ref "C17") (pin "1") (pinfunction "1_1") (pintype "passive"))
      (node (ref "C18") (pin "2") (pinfunction "2_2") (pintype "passive"))
      (node (ref "C19") (pin "1") (pinfunction "1_1") (pintype "passive"))
      (node (ref "C2") (pin "1") (pinfunction "1_1") (pintype "passive"))
      (node (ref "C20") (pin "2") (pinfunction "2_2") (pintype "passive"))
      (node (ref "C21") (pin "2") (pinfunction "2_2") (pintype "passive"))
      (node (ref "C22") (pin "2") (pinfunction "2_2") (pintype "passive"))
      (node (ref "C23") (pin "2") (pinfunction "2_2") (pintype "passive"))
      (node (ref "C24") (pin "2") (pinfunction "2_2") (pintype "passive"))
      (node (ref "C29") (pin "1") (pinfunction "1_1") (pintype "passive"))
      (node (ref "C3") (pin "1") (pinfunction "1_1") (pintype "passive"))
      (node (ref "C30") (pin "1") (pinfunction "1_1") (pintype "passive"))
      (node (ref "C31") (pin "1") (pinfunction "1_1") (pintype "passive"))
      (node (ref "C32") (pin "1") (pinfunction "1_1") (pintype "passive"))
      (node (ref "C33") (pin "2") (pinfunction "2_2") (pintype "passive"))
      (node (ref "C34") (pin "1") (pinfunction "1_1") (pintype "passive"))
      (node (ref "C35") (pin "1") (pinfunction "1_1") (pintype "passive"))
      (node (ref "C36") (pin "1") (pinfunction "1_1") (pintype "passive"))
      (node (ref "C37") (pin "2") (pinfunction "2_2") (pintype "passive"))
      (node (ref "C38") (pin "1") (pinfunction "1_1") (pintype "passive"))
      (node (ref "C39") (pin "1") (pinfunction "1_1") (pintype "passive"))
      (node (ref "C4") (pin "2") (pinfunction "2_2") (pintype "passive"))
      (node (ref "C5") (pin "2") (pinfunction "2_2") (pintype "passive"))
      (node (ref "C6") (pin "1") (pinfunction "1_1") (pintype "passive"))
      (node (ref "C7") (pin "1") (pinfunction "1_1") (pintype "passive"))
      (node (ref "C8") (pin "1") (pinfunction "1_1") (pintype "passive"))
      (node (ref "C9") (pin "2") (pinfunction "2_2") (pintype "passive"))
      (node (ref "D10") (pin "1") (pinfunction "1_1") (pintype "passive"))
      (node (ref "D11") (pin "1") (pinfunction "1_1") (pintype "passive"))
      (node (ref "D12") (pin "2") (pinfunction "CATHODE_2") (pintype "passive"))
      (node (ref "D5") (pin "1") (pinfunction "1_1") (pintype "passive"))
      (node (ref "D6") (pin "2") (pinfunction "A_2") (pintype "passive"))
      (node (ref "D9") (pin "2") (pinfunction "A_2") (pintype "passive"))
      (node (ref "DP3") (pin "1") (pintype "passive"))
      (node (ref "E1") (pin "2") (pinfunction "GND_2") (pintype "passive"))
      (node (ref "J1") (pin "6") (pinfunction "VSS_6") (pintype "passive"))
      (node (ref "J1") (pin "SH1") (pinfunction "GND1_SH1") (pintype "passive"))
      (node (ref "J1") (pin "SH2") (pinfunction "GND2_SH2") (pintype "passive"))
      (node (ref "J1") (pin "SH3") (pinfunction "GND3_SH3") (pintype "passive"))
      (node (ref "J1") (pin "SH4") (pinfunction "GND4_SH4") (pintype "passive"))
      (node (ref "J3") (pin "2") (pinfunction "SLEEVE_2") (pintype "power_in"))
      (node (ref "J3") (pin "3") (pinfunction "INSERTION_DET_3") (pintype "power_in"))
      (node (ref "J4") (pin "2") (pinfunction "2_2") (pintype "passive"))
      (node (ref "J6") (pin "2") (pinfunction "G1_2") (pintype "passive"))
      (node (ref "J6") (pin "3") (pinfunction "G2_3") (pintype "passive"))
      (node (ref "J8") (pin "2") (pinfunction "G1_2") (pintype "passive"))
      (node (ref "LM1") (pin "3") (pinfunction "GND_3") (pintype "passive"))
      (node (ref "M1") (pin "1") (pinfunction "1_1") (pintype "passive"))
      (node (ref "M2") (pin "1") (pinfunction "1_1") (pintype "passive"))
      (node (ref "M3") (pin "1") (pinfunction "1_1") (pintype "passive"))
      (node (ref "M4") (pin "1") (pinfunction "1_1") (pintype "passive"))
      (node (ref "Q1") (pin "2") (pinfunction "E_2") (pintype "passive"))
      (node (ref "Q2") (pin "2") (pinfunction "E_2") (pintype "passive"))
      (node (ref "Q3") (pin "2") (pinfunction "E_2") (pintype "passive"))
      (node (ref "Q4") (pin "2") (pinfunction "E_2") (pintype "passive"))
      (node (ref "Q5") (pin "2") (pinfunction "E_2") (pintype "passive"))
      (node (ref "Q6") (pin "2") (pinfunction "E_2") (pintype "passive"))
      (node (ref "Q7") (pin "2") (pinfunction "E_2") (pintype "passive"))
      (node (ref "R12") (pin "1") (pinfunction "1_1") (pintype "passive"))
      (node (ref "R13") (pin "1") (pinfunction "1_1") (pintype "passive"))
      (node (ref "R14") (pin "1") (pinfunction "1_1") (pintype "passive"))
      (node (ref "R15") (pin "1") (pinfunction "1_1") (pintype "passive"))
      (node (ref "R33") (pin "1") (pinfunction "1_1") (pintype "passive"))
      (node (ref "R34") (pin "1") (pinfunction "1_1") (pintype "passive"))
      (node (ref "R35") (pin "1") (pinfunction "1_1") (pintype "passive"))
      (node (ref "R37") (pin "1") (pinfunction "1_1") (pintype "passive"))
      (node (ref "R42") (pin "1") (pinfunction "1_1") (pintype "passive"))
      (node (ref "R46") (pin "1") (pinfunction "1_1") (pintype "passive"))
      (node (ref "R52") (pin "1") (pinfunction "1_1") (pintype "passive"))
      (node (ref "R6") (pin "1") (pinfunction "1_1") (pintype "passive"))
      (node (ref "SIM1") (pin "1") (pinfunction "GND_1") (pintype "passive"))
      (node (ref "SIM1") (pin "18") (pinfunction "GND_18") (pintype "passive"))
      (node (ref "SIM1") (pin "2") (pinfunction "GND_2") (pintype "passive"))
      (node (ref "SIM1") (pin "28") (pinfunction "GND_28") (pintype "passive"))
      (node (ref "SIM1") (pin "3") (pinfunction "GND_3") (pintype "passive"))
      (node (ref "SIM1") (pin "34") (pinfunction "GND_34") (pintype "passive"))
      (node (ref "SIM1") (pin "36") (pinfunction "GND_36") (pintype "passive"))
      (node (ref "SIM1") (pin "40") (pinfunction "GND_40") (pintype "passive"))
      (node (ref "SIM1") (pin "51") (pinfunction "GND_51") (pintype "passive"))
      (node (ref "SIM1") (pin "52") (pinfunction "GND_52") (pintype "passive"))
      (node (ref "SIM1") (pin "54") (pinfunction "GND_54") (pintype "passive"))
      (node (ref "SIM1") (pin "64") (pinfunction "GND_64") (pintype "passive"))
      (node (ref "SIM1") (pin "65") (pinfunction "GND_65") (pintype "passive"))
      (node (ref "SIM1") (pin "67") (pinfunction "GND_67") (pintype "passive"))
      (node (ref "SIM1") (pin "68") (pinfunction "GND_68") (pintype "passive"))
      (node (ref "SW1") (pin "1") (pinfunction "P1_1") (pintype "passive"))
      (node (ref "SW2") (pin "1") (pinfunction "P1_1") (pintype "passive"))
      (node (ref "SW3") (pin "1") (pinfunction "P1_1") (pintype "passive"))
      (node (ref "SW4") (pin "1") (pinfunction "P1_1") (pintype "passive"))
      (node (ref "SW5") (pin "1") (pinfunction "P1_1") (pintype "passive"))
      (node (ref "SW8") (pin "2") (pinfunction "P3_2") (pintype "passive"))
      (node (ref "SW9") (pin "2") (pinfunction "P3_2") (pintype "passive"))
      (node (ref "U1") (pin "1") (pinfunction "GND_1") (pintype "power_in"))
      (node (ref "U1") (pin "15") (pinfunction "GND_15") (pintype "power_in"))
      (node (ref "U1") (pin "38") (pinfunction "GND_38") (pintype "power_in"))
      (node (ref "U1") (pin "39_1") (pinfunction "GND_39_1") (pintype "power_in"))
      (node (ref "U1") (pin "39_10") (pinfunction "GND_39_10") (pintype "power_in"))
      (node (ref "U1") (pin "39_11") (pinfunction "GND_39_11") (pintype "power_in"))
      (node (ref "U1") (pin "39_12") (pinfunction "GND_39_12") (pintype "power_in"))
      (node (ref "U1") (pin "39_13") (pinfunction "GND_39_13") (pintype "power_in"))
      (node (ref "U1") (pin "39_14") (pinfunction "GND_39_14") (pintype "power_in"))
      (node (ref "U1") (pin "39_15") (pinfunction "GND_39_15") (pintype "power_in"))
      (node (ref "U1") (pin "39_16") (pinfunction "GND_39_16") (pintype "power_in"))
      (node (ref "U1") (pin "39_17") (pinfunction "GND_39_17") (pintype "power_in"))
      (node (ref "U1") (pin "39_18") (pinfunction "GND_39_18") (pintype "power_in"))
      (node (ref "U1") (pin "39_19") (pinfunction "GND_39_19") (pintype "power_in"))
      (node (ref "U1") (pin "39_2") (pinfunction "GND_39_2") (pintype "power_in"))
      (node (ref "U1") (pin "39_20") (pinfunction "GND_39_20") (pintype "power_in"))
      (node (ref "U1") (pin "39_21") (pinfunction "GND_39_21") (pintype "power_in"))
      (node (ref "U1") (pin "39_3") (pinfunction "GND_39_3") (pintype "power_in"))
      (node (ref "U1") (pin "39_4") (pinfunction "GND_39_4") (pintype "power_in"))
      (node (ref "U1") (pin "39_5") (pinfunction "GND_39_5") (pintype "power_in"))
      (node (ref "U1") (pin "39_6") (pinfunction "GND_39_6") (pintype "power_in"))
      (node (ref "U1") (pin "39_7") (pinfunction "GND_39_7") (pintype "power_in"))
      (node (ref "U1") (pin "39_8") (pinfunction "GND_39_8") (pintype "power_in"))
      (node (ref "U1") (pin "39_9") (pinfunction "GND_39_9") (pintype "power_in"))
      (node (ref "U2") (pin "4") (pinfunction "GND_4") (pintype "passive"))
      (node (ref "U3") (pin "1") (pinfunction "GND_1") (pintype "passive"))
      (node (ref "U4") (pin "18") (pinfunction "GND_18") (pintype "power_in"))
      (node (ref "U4") (pin "21") (pinfunction "GND_21") (pintype "power_in"))
      (node (ref "U4") (pin "25") (pinfunction "AGND_25") (pintype "power_in"))
      (node (ref "U4") (pin "26") (pinfunction "TEST_26") (pintype "input"))
      (node (ref "U4") (pin "7") (pinfunction "GND_7") (pintype "power_in"))
      (node (ref "U5") (pin "1") (pinfunction "GND_1") (pintype "power_in"))
      (node (ref "UP1") (pin "3") (pinfunction "GND_3") (pintype "power_in"))
      (node (ref "UP1") (pin "5") (pinfunction "ON#/OFF_5") (pintype "passive"))
      (node (ref "UP1") (pin "6") (pinfunction "EPAD_6") (pintype "passive"))
      (node (ref "USB1") (pin "A1B12") (pinfunction "GND_A1B12") (pintype "passive"))
      (node (ref "USB1") (pin "B1A12") (pinfunction "GND_B1A12") (pintype "passive"))
      (node (ref "USB1") (pin "SH1") (pinfunction "SH1_SH1") (pintype "passive"))
      (node (ref "USB1") (pin "SH2") (pinfunction "SH2_SH2") (pintype "passive"))
      (node (ref "USB1") (pin "SH3") (pinfunction "SH3_SH3") (pintype "passive"))
      (node (ref "USB1") (pin "SH4") (pinfunction "SH4_SH4") (pintype "passive"))
    )
    (net (code "63") (name "Net-(D1-ANODE)") (class "Default")
      (node (ref "D1") (pin "1") (pinfunction "ANODE_1") (pintype "passive"))
      (node (ref "R2") (pin "1") (pinfunction "1_1") (pintype "passive"))
    )
    (net (code "64") (name "Net-(D1-CATHODE)") (class "Default")
      (node (ref "D1") (pin "2") (pinfunction "CATHODE_2") (pintype "passive"))
      (node (ref "Q1") (pin "3") (pinfunction "C_3") (pintype "passive"))
    )
    (net (code "65") (name "Net-(D2-ANODE)") (class "Default")
      (node (ref "D2") (pin "1") (pinfunction "ANODE_1") (pintype "passive"))
      (node (ref "R3") (pin "1") (pinfunction "1_1") (pintype "passive"))
    )
    (net (code "66") (name "Net-(D2-CATHODE)") (class "Default")
      (node (ref "D2") (pin "2") (pinfunction "CATHODE_2") (pintype "passive"))
      (node (ref "Q2") (pin "3") (pinfunction "C_3") (pintype "passive"))
    )
    (net (code "67") (name "Net-(D3-ANODE)") (class "Default")
      (node (ref "D3") (pin "1") (pinfunction "ANODE_1") (pintype "passive"))
      (node (ref "R4") (pin "1") (pinfunction "1_1") (pintype "passive"))
    )
    (net (code "68") (name "Net-(D3-CATHODE)") (class "Default")
      (node (ref "D3") (pin "2") (pinfunction "CATHODE_2") (pintype "passive"))
      (node (ref "Q3") (pin "3") (pinfunction "C_3") (pintype "passive"))
    )
    (net (code "69") (name "Net-(D4-ANODE)") (class "Default")
      (node (ref "D4") (pin "1") (pinfunction "ANODE_1") (pintype "passive"))
      (node (ref "R5") (pin "1") (pinfunction "1_1") (pintype "passive"))
    )
    (net (code "70") (name "Net-(D4-CATHODE)") (class "Default")
      (node (ref "D4") (pin "2") (pinfunction "CATHODE_2") (pintype "passive"))
      (node (ref "Q4") (pin "3") (pinfunction "C_3") (pintype "passive"))
    )
    (net (code "71") (name "Net-(D6-C2)") (class "Default")
      (node (ref "D6") (pin "3") (pinfunction "C2_3") (pintype "passive"))
      (node (ref "R18") (pin "1") (pinfunction "1_1") (pintype "passive"))
      (node (ref "U2") (pin "6") (pinfunction "SIM_DATA_6") (pintype "passive"))
    )
    (net (code "72") (name "Net-(D6-C3)") (class "Default")
      (node (ref "D6") (pin "4") (pinfunction "C3_4") (pintype "passive"))
      (node (ref "R21") (pin "2") (pinfunction "2_2") (pintype "passive"))
      (node (ref "U2") (pin "2") (pinfunction "SIM_RST_2") (pintype "passive"))
    )
    (net (code "73") (name "Net-(D6-C4)") (class "Default")
      (node (ref "D6") (pin "5") (pinfunction "C4_5") (pintype "passive"))
      (node (ref "R22") (pin "2") (pinfunction "2_2") (pintype "passive"))
      (node (ref "U2") (pin "3") (pinfunction "SIM_CLK_3") (pintype "passive"))
    )
    (net (code "74") (name "Net-(D7-ANODE)") (class "Default")
      (node (ref "D7") (pin "1") (pinfunction "ANODE_1") (pintype "passive"))
      (node (ref "R43") (pin "2") (pinfunction "2_2") (pintype "passive"))
    )
    (net (code "75") (name "Net-(D7-CATHODE)") (class "Default")
      (node (ref "D7") (pin "2") (pinfunction "CATHODE_2") (pintype "passive"))
      (node (ref "U4") (pin "23") (pinfunction "CBUS0_23") (pintype "bidirectional"))
    )
    (net (code "76") (name "Net-(D8-ANODE)") (class "Default")
      (node (ref "D8") (pin "1") (pinfunction "ANODE_1") (pintype "passive"))
      (node (ref "R44") (pin "2") (pinfunction "2_2") (pintype "passive"))
    )
    (net (code "77") (name "Net-(D8-CATHODE)") (class "Default")
      (node (ref "D8") (pin "2") (pinfunction "CATHODE_2") (pintype "passive"))
      (node (ref "U4") (pin "22") (pinfunction "CBUS1_22") (pintype "bidirectional"))
    )
    (net (code "78") (name "Net-(D12-ANODE)") (class "Default")
      (node (ref "D12") (pin "1") (pinfunction "ANODE_1") (pintype "passive"))
      (node (ref "R56") (pin "2") (pinfunction "2_2") (pintype "passive"))
    )
    (net (code "79") (name "Net-(DP2-Pad1)") (class "Default")
      (node (ref "DP2") (pin "1") (pintype "passive"))
      (node (ref "USB1") (pin "A4B9") (pinfunction "VBUS_A4B9") (pintype "passive"))
      (node (ref "USB1") (pin "B4A9") (pinfunction "VBUS_B4A9") (pintype "passive"))
    )
    (net (code "80") (name "Net-(DP2-Pad2)") (class "Default")
      (node (ref "DP2") (pin "2") (pintype "passive"))
      (node (ref "F1") (pin "2") (pinfunction "2_2") (pintype "passive"))
    )
    (net (code "81") (name "Net-(J3-TIP)") (class "Default")
      (node (ref "C23") (pin "1") (pinfunction "1_1") (pintype "passive"))
      (node (ref "J3") (pin "1") (pinfunction "TIP_1") (pintype "power_in"))
      (node (ref "UP1") (pin "1") (pinfunction "VIN_1") (pintype "power_in"))
    )
    (net (code "82") (name "Net-(J5-Pad1)") (class "Default")
      (node (ref "J5") (pin "1") (pinfunction "1_1") (pintype "passive"))
      (node (ref "R48") (pin "1") (pinfunction "1_1") (pintype "passive"))
    )
    (net (code "83") (name "Net-(J5-Pad2)") (class "Default")
      (node (ref "J5") (pin "2") (pinfunction "2_2") (pintype "passive"))
      (node (ref "R49") (pin "2") (pinfunction "2_2") (pintype "passive"))
    )
    (net (code "84") (name "Net-(L2-Pad2)") (class "Default")
      (node (ref "L2") (pin "2") (pinfunction "2_2") (pintype "passive"))
      (node (ref "R47") (pin "2") (pinfunction "2_2") (pintype "passive"))
    )
    (net (code "85") (name "Net-(Q1-B)") (class "Default")
      (node (ref "Q1") (pin "1") (pinfunction "B_1") (pintype "passive"))
      (node (ref "R12") (pin "2") (pinfunction "2_2") (pintype "passive"))
      (node (ref "R7") (pin "2") (pinfunction "2_2") (pintype "passive"))
    )
    (net (code "86") (name "Net-(Q2-B)") (class "Default")
      (node (ref "Q2") (pin "1") (pinfunction "B_1") (pintype "passive"))
      (node (ref "R13") (pin "2") (pinfunction "2_2") (pintype "passive"))
      (node (ref "R8") (pin "2") (pinfunction "2_2") (pintype "passive"))
    )
    (net (code "87") (name "Net-(Q3-B)") (class "Default")
      (node (ref "Q3") (pin "1") (pinfunction "B_1") (pintype "passive"))
      (node (ref "R14") (pin "2") (pinfunction "2_2") (pintype "passive"))
      (node (ref "R9") (pin "2") (pinfunction "2_2") (pintype "passive"))
    )
    (net (code "88") (name "Net-(Q4-B)") (class "Default")
      (node (ref "Q4") (pin "1") (pinfunction "B_1") (pintype "passive"))
      (node (ref "R10") (pin "2") (pinfunction "2_2") (pintype "passive"))
      (node (ref "R15") (pin "2") (pinfunction "2_2") (pintype "passive"))
    )
    (net (code "89") (name "Net-(Q5-B)") (class "Default")
      (node (ref "Q5") (pin "1") (pinfunction "B_1") (pintype "passive"))
      (node (ref "R30") (pin "2") (pinfunction "2_2") (pintype "passive"))
      (node (ref "R33") (pin "2") (pinfunction "2_2") (pintype "passive"))
    )
    (net (code "90") (name "Net-(Q6-B)") (class "Default")
      (node (ref "Q6") (pin "1") (pinfunction "B_1") (pintype "passive"))
      (node (ref "R31") (pin "2") (pinfunction "2_2") (pintype "passive"))
      (node (ref "R34") (pin "2") (pinfunction "2_2") (pintype "passive"))
    )
    (net (code "91") (name "Net-(Q7-B)") (class "Default")
      (node (ref "Q7") (pin "1") (pinfunction "B_1") (pintype "passive"))
      (node (ref "R32") (pin "2") (pinfunction "2_2") (pintype "passive"))
      (node (ref "R37") (pin "2") (pinfunction "2_2") (pintype "passive"))
    )
    (net (code "92") (name "Net-(Q7-C)") (class "Default")
      (node (ref "DP1") (pin "1") (pintype "passive"))
      (node (ref "J2") (pin "2") (pinfunction "2_2") (pintype "passive"))
      (node (ref "Q7") (pin "3") (pinfunction "C_3") (pintype "passive"))
    )
    (net (code "93") (name "Net-(Q8-B)") (class "Default")
      (node (ref "Q8") (pin "1") (pinfunction "B_1") (pintype "passive"))
      (node (ref "R54") (pin "2") (pinfunction "2_2") (pintype "passive"))
    )
    (net (code "94") (name "Net-(Q9-B)") (class "Default")
      (node (ref "Q9") (pin "1") (pinfunction "B_1") (pintype "passive"))
      (node (ref "R58") (pin "2") (pinfunction "2_2") (pintype "passive"))
    )
    (net (code "95") (name "Net-(SIM1-RI)") (class "Default")
      (node (ref "R16") (pin "1") (pinfunction "1_1") (pintype "passive"))
      (node (ref "SIM1") (pin "10") (pinfunction "RI_10") (pintype "passive"))
    )
    (net (code "96") (name "Net-(U4-OSCI)") (class "Default")
      (node (ref "C33") (pin "1") (pinfunction "1_1") (pintype "passive"))
      (node (ref "U4") (pin "27") (pinfunction "OSCI_27") (pintype "input"))
      (node (ref "X1") (pin "2") (pinfunction "OSC2_2") (pintype "passive"))
    )
    (net (code "97") (name "Net-(U4-OSCO)") (class "Default")
      (node (ref "C37") (pin "1") (pinfunction "1_1") (pintype "passive"))
      (node (ref "U4") (pin "28") (pinfunction "OSCO_28") (pintype "output"))
      (node (ref "X1") (pin "1") (pinfunction "OSC1_1") (pintype "passive"))
    )
    (net (code "98") (name "Net-(U4-RXD)") (class "Default")
      (node (ref "R41") (pin "2") (pinfunction "2_2") (pintype "passive"))
      (node (ref "U4") (pin "5") (pinfunction "RXD_5") (pintype "input"))
    )
    (net (code "99") (name "Net-(U4-TXD)") (class "Default")
      (node (ref "R40") (pin "2") (pinfunction "2_2") (pintype "passive"))
      (node (ref "U4") (pin "1") (pinfunction "TXD_1") (pintype "output"))
    )
    (net (code "100") (name "Net-(U4-VCCIO)") (class "Default")
      (node (ref "R39") (pin "2") (pinfunction "2_2") (pintype "passive"))
      (node (ref "U4") (pin "4") (pinfunction "VCCIO_4") (pintype "power_in"))
    )
    (net (code "101") (name "Net-(U4-~{RESET})") (class "Default")
      (node (ref "R45") (pin "1") (pinfunction "1_1") (pintype "passive"))
      (node (ref "R46") (pin "2") (pinfunction "2_2") (pintype "passive"))
      (node (ref "U4") (pin "19") (pinfunction "~{RESET}_19") (pintype "input"))
    )
    (net (code "102") (name "Net-(UP1-OUT)") (class "Default")
      (node (ref "DP3") (pin "2") (pintype "passive"))
      (node (ref "L1") (pin "1") (pinfunction "1_1") (pintype "passive"))
      (node (ref "UP1") (pin "2") (pinfunction "OUT_2") (pintype "power_in"))
    )
    (net (code "103") (name "USB_3V3") (class "Default")
      (node (ref "C22") (pin "1") (pinfunction "1_1") (pintype "passive"))
      (node (ref "R39") (pin "1") (pinfunction "1_1") (pintype "passive"))
      (node (ref "U4") (pin "17") (pinfunction "3V3OUT_17") (pintype "output"))
    )
    (net (code "104") (name "VBAT") (class "Default")
      (node (ref "C34") (pin "2") (pinfunction "2_2") (pintype "passive"))
      (node (ref "C4") (pin "1") (pinfunction "1_1") (pintype "passive"))
      (node (ref "C6") (pin "2") (pinfunction "2_2") (pintype "passive"))
      (node (ref "C7") (pin "2") (pinfunction "2_2") (pintype "passive"))
      (node (ref "C8") (pin "2") (pinfunction "2_2") (pintype "passive"))
      (node (ref "D5") (pin "2") (pinfunction "2_2") (pintype "passive"))
      (node (ref "DP1") (pin "2") (pintype "passive"))
      (node (ref "J2") (pin "1") (pinfunction "1_1") (pintype "passive"))
      (node (ref "J4") (pin "1") (pinfunction "1_1") (pintype "passive"))
      (node (ref "R2") (pin "2") (pinfunction "2_2") (pintype "passive"))
      (node (ref "R3") (pin "2") (pinfunction "2_2") (pintype "passive"))
      (node (ref "R4") (pin "2") (pinfunction "2_2") (pintype "passive"))
      (node (ref "R47") (pin "1") (pinfunction "1_1") (pintype "passive"))
      (node (ref "R5") (pin "2") (pinfunction "2_2") (pintype "passive"))
      (node (ref "SIM1") (pin "4") (pinfunction "VBAT_4") (pintype "passive"))
      (node (ref "SIM1") (pin "5") (pinfunction "VBAT_5") (pintype "passive"))
      (node (ref "SIM1") (pin "6") (pinfunction "VBAT_6") (pintype "passive"))
      (node (ref "U5") (pin "3") (pinfunction "IN_3") (pintype "power_in"))
    )
    (net (code "105") (name "VRTC") (class "Default")
      (node (ref "C5") (pin "1") (pinfunction "1_1") (pintype "passive"))
      (node (ref "SIM1") (pin "17") (pinfunction "VRTC_17") (pintype "passive"))
    )
    (net (code "106") (name "unconnected-(D6-C1-Pad1)") (class "Default")
      (node (ref "D6") (pin "1") (pinfunction "C1_1") (pintype "passive+no_connect"))
    )
    (net (code "107") (name "unconnected-(D9-C5-Pad6)") (class "Default")
      (node (ref "D9") (pin "6") (pinfunction "C5_6") (pintype "passive+no_connect"))
    )
    (net (code "108") (name "unconnected-(J1-CD-Pad9)") (class "Default")
      (node (ref "J1") (pin "9") (pinfunction "CD_9") (pintype "passive+no_connect"))
    )
    (net (code "109") (name "unconnected-(SIM1-ADC0-Pad23)") (class "Default")
      (node (ref "SIM1") (pin "23") (pinfunction "ADC0_23") (pintype "passive+no_connect"))
    )
    (net (code "110") (name "unconnected-(SIM1-ADC1-Pad24)") (class "Default")
      (node (ref "SIM1") (pin "24") (pinfunction "ADC1_24") (pintype "passive+no_connect"))
    )
    (net (code "111") (name "unconnected-(SIM1-CTS-Pad12)") (class "Default")
      (node (ref "SIM1") (pin "12") (pinfunction "CTS_12") (pintype "passive+no_connect"))
    )
    (net (code "112") (name "unconnected-(SIM1-DCD-Pad11)") (class "Default")
      (node (ref "SIM1") (pin "11") (pinfunction "DCD_11") (pintype "passive+no_connect"))
    )
    (net (code "113") (name "unconnected-(SIM1-GPIO17-Pad44)") (class "Default")
      (node (ref "SIM1") (pin "44") (pinfunction "GPIO17_44") (pintype "passive+no_connect"))
    )
    (net (code "114") (name "unconnected-(SIM1-GPIO19-Pad43)") (class "Default")
      (node (ref "SIM1") (pin "43") (pinfunction "GPIO19_43") (pintype "passive+no_connect"))
    )
    (net (code "115") (name "unconnected-(SIM1-KBC0-Pad62)") (class "Default")
      (node (ref "SIM1") (pin "62") (pinfunction "KBC0_62") (pintype "passive+no_connect"))
    )
    (net (code "116") (name "unconnected-(SIM1-KBC1-Pad61)") (class "Default")
      (node (ref "SIM1") (pin "61") (pinfunction "KBC1_61") (pintype "passive+no_connect"))
    )
    (net (code "117") (name "unconnected-(SIM1-KBC2-Pad60)") (class "Default")
      (node (ref "SIM1") (pin "60") (pinfunction "KBC2_60") (pintype "passive+no_connect"))
    )
    (net (code "118") (name "unconnected-(SIM1-KBC3-Pad59)") (class "Default")
      (node (ref "SIM1") (pin "59") (pinfunction "KBC3_59") (pintype "passive+no_connect"))
    )
    (net (code "119") (name "unconnected-(SIM1-KBR0-Pad58)") (class "Default")
      (node (ref "SIM1") (pin "58") (pinfunction "KBR0_58") (pintype "passive+no_connect"))
    )
    (net (code "120") (name "unconnected-(SIM1-KBR1-Pad57)") (class "Default")
      (node (ref "SIM1") (pin "57") (pinfunction "KBR1_57") (pintype "passive+no_connect"))
    )
    (net (code "121") (name "unconnected-(SIM1-KBR2-Pad56)") (class "Default")
      (node (ref "SIM1") (pin "56") (pinfunction "KBR2_56") (pintype "passive+no_connect"))
    )
    (net (code "122") (name "unconnected-(SIM1-KBR3-Pad55)") (class "Default")
      (node (ref "SIM1") (pin "55") (pinfunction "KBR3_55") (pintype "passive+no_connect"))
    )
    (net (code "123") (name "unconnected-(SIM1-PCM_CLK-Pad46)") (class "Default")
      (node (ref "SIM1") (pin "46") (pinfunction "PCM_CLK_46") (pintype "passive+no_connect"))
    )
    (net (code "124") (name "unconnected-(SIM1-PCM_IN-Pad47)") (class "Default")
      (node (ref "SIM1") (pin "47") (pinfunction "PCM_IN_47") (pintype "passive+no_connect"))
    )
    (net (code "125") (name "unconnected-(SIM1-PCM_OUT-Pad48)") (class "Default")
      (node (ref "SIM1") (pin "48") (pinfunction "PCM_OUT_48") (pintype "passive+no_connect"))
    )
    (net (code "126") (name "unconnected-(SIM1-PCM_SYNC-Pad45)") (class "Default")
      (node (ref "SIM1") (pin "45") (pinfunction "PCM_SYNC_45") (pintype "passive+no_connect"))
    )
    (net (code "127") (name "unconnected-(SIM1-PWM1-Pad42)") (class "Default")
      (node (ref "SIM1") (pin "42") (pinfunction "PWM1_42") (pintype "passive+no_connect"))
    )
    (net (code "128") (name "unconnected-(SIM1-PWM2-Pad41)") (class "Default")
      (node (ref "SIM1") (pin "41") (pinfunction "PWM2_41") (pintype "passive+no_connect"))
    )
    (net (code "129") (name "unconnected-(SIM1-RF_SYNC-Pad63)") (class "Default")
      (node (ref "SIM1") (pin "63") (pinfunction "RF_SYNC_63") (pintype "passive+no_connect"))
    )
    (net (code "130") (name "unconnected-(SIM1-RTS-Pad13)") (class "Default")
      (node (ref "SIM1") (pin "13") (pinfunction "RTS_13") (pintype "passive+no_connect"))
    )
    (net (code "131") (name "unconnected-(SIM1-SCL-Pad39)") (class "Default")
      (node (ref "SIM1") (pin "39") (pinfunction "SCL_39") (pintype "passive+no_connect"))
    )
    (net (code "132") (name "unconnected-(SIM1-SDA-Pad38)") (class "Default")
      (node (ref "SIM1") (pin "38") (pinfunction "SDA_38") (pintype "passive+no_connect"))
    )
    (net (code "133") (name "unconnected-(SIM1-SIM_DET-Pad33)") (class "Default")
      (node (ref "SIM1") (pin "33") (pinfunction "SIM_DET_33") (pintype "passive+no_connect"))
    )
    (net (code "134") (name "unconnected-(SIM1-VCHG-Pad25)") (class "Default")
      (node (ref "SIM1") (pin "25") (pinfunction "VCHG_25") (pintype "passive+no_connect"))
    )
    (net (code "135") (name "unconnected-(SIM1-VDD_EXT-Pad7)") (class "Default")
      (node (ref "SIM1") (pin "7") (pinfunction "VDD_EXT_7") (pintype "passive+no_connect"))
    )
    (net (code "136") (name "unconnected-(U1-SCK{slash}CLK-Pad20)") (class "Default")
      (node (ref "U1") (pin "20") (pinfunction "SCK/CLK_20") (pintype "bidirectional+no_connect"))
    )
    (net (code "137") (name "unconnected-(U1-SCS{slash}CMD-Pad19)") (class "Default")
      (node (ref "U1") (pin "19") (pinfunction "SCS/CMD_19") (pintype "bidirectional+no_connect"))
    )
    (net (code "138") (name "unconnected-(U1-SDI{slash}SD1-Pad22)") (class "Default")
      (node (ref "U1") (pin "22") (pinfunction "SDI/SD1_22") (pintype "bidirectional+no_connect"))
    )
    (net (code "139") (name "unconnected-(U1-SDO{slash}SD0-Pad21)") (class "Default")
      (node (ref "U1") (pin "21") (pinfunction "SDO/SD0_21") (pintype "bidirectional+no_connect"))
    )
    (net (code "140") (name "unconnected-(U1-SHD{slash}SD2-Pad17)") (class "Default")
      (node (ref "U1") (pin "17") (pinfunction "SHD/SD2_17") (pintype "bidirectional+no_connect"))
    )
    (net (code "141") (name "unconnected-(U1-SWP{slash}SD3-Pad18)") (class "Default")
      (node (ref "U1") (pin "18") (pinfunction "SWP/SD3_18") (pintype "bidirectional+no_connect"))
    )
    (net (code "142") (name "unconnected-(U2-SIM_VPP-Pad5)") (class "Default")
      (node (ref "U2") (pin "5") (pinfunction "SIM_VPP_5") (pintype "passive+no_connect"))
    )
    (net (code "143") (name "unconnected-(U4-CBUS2-Pad13)") (class "Default")
      (node (ref "U4") (pin "13") (pinfunction "CBUS2_13") (pintype "bidirectional+no_connect"))
    )
    (net (code "144") (name "unconnected-(U4-CBUS3-Pad14)") (class "Default")
      (node (ref "U4") (pin "14") (pinfunction "CBUS3_14") (pintype "bidirectional+no_connect"))
    )
    (net (code "145") (name "unconnected-(U4-CBUS4-Pad12)") (class "Default")
      (node (ref "U4") (pin "12") (pinfunction "CBUS4_12") (pintype "bidirectional+no_connect"))
    )
    (net (code "146") (name "unconnected-(U4-NC-Pad8)") (class "Default")
      (node (ref "U4") (pin "8") (pinfunction "NC_8") (pintype "passive+no_connect"))
    )
    (net (code "147") (name "unconnected-(U4-NC-Pad24)") (class "Default")
      (node (ref "U4") (pin "24") (pinfunction "NC_24") (pintype "passive+no_connect"))
    )
    (net (code "148") (name "unconnected-(U4-~{CTS}-Pad11)") (class "Default")
      (node (ref "U4") (pin "11") (pinfunction "~{CTS}_11") (pintype "input+no_connect"))
    )
    (net (code "149") (name "unconnected-(U4-~{DCD}-Pad10)") (class "Default")
      (node (ref "U4") (pin "10") (pinfunction "~{DCD}_10") (pintype "input+no_connect"))
    )
    (net (code "150") (name "unconnected-(U4-~{DSR}-Pad9)") (class "Default")
      (node (ref "U4") (pin "9") (pinfunction "~{DSR}_9") (pintype "input+no_connect"))
    )
    (net (code "151") (name "unconnected-(U4-~{RI}-Pad6)") (class "Default")
      (node (ref "U4") (pin "6") (pinfunction "~{RI}_6") (pintype "input+no_connect"))
    )
    (net (code "152") (name "unconnected-(USB1-SBU1-PadA8)") (class "Default")
      (node (ref "USB1") (pin "A8") (pinfunction "SBU1_A8") (pintype "passive+no_connect"))
    )
    (net (code "153") (name "unconnected-(USB1-SBU2-PadB8)") (class "Default")
      (node (ref "USB1") (pin "B8") (pinfunction "SBU2_B8") (pintype "passive+no_connect"))
    )
  )
)
